# zx80_SD_12_smd_build006_9_STM32.net
KiCad netlist of a schematic drawn in EAGLE
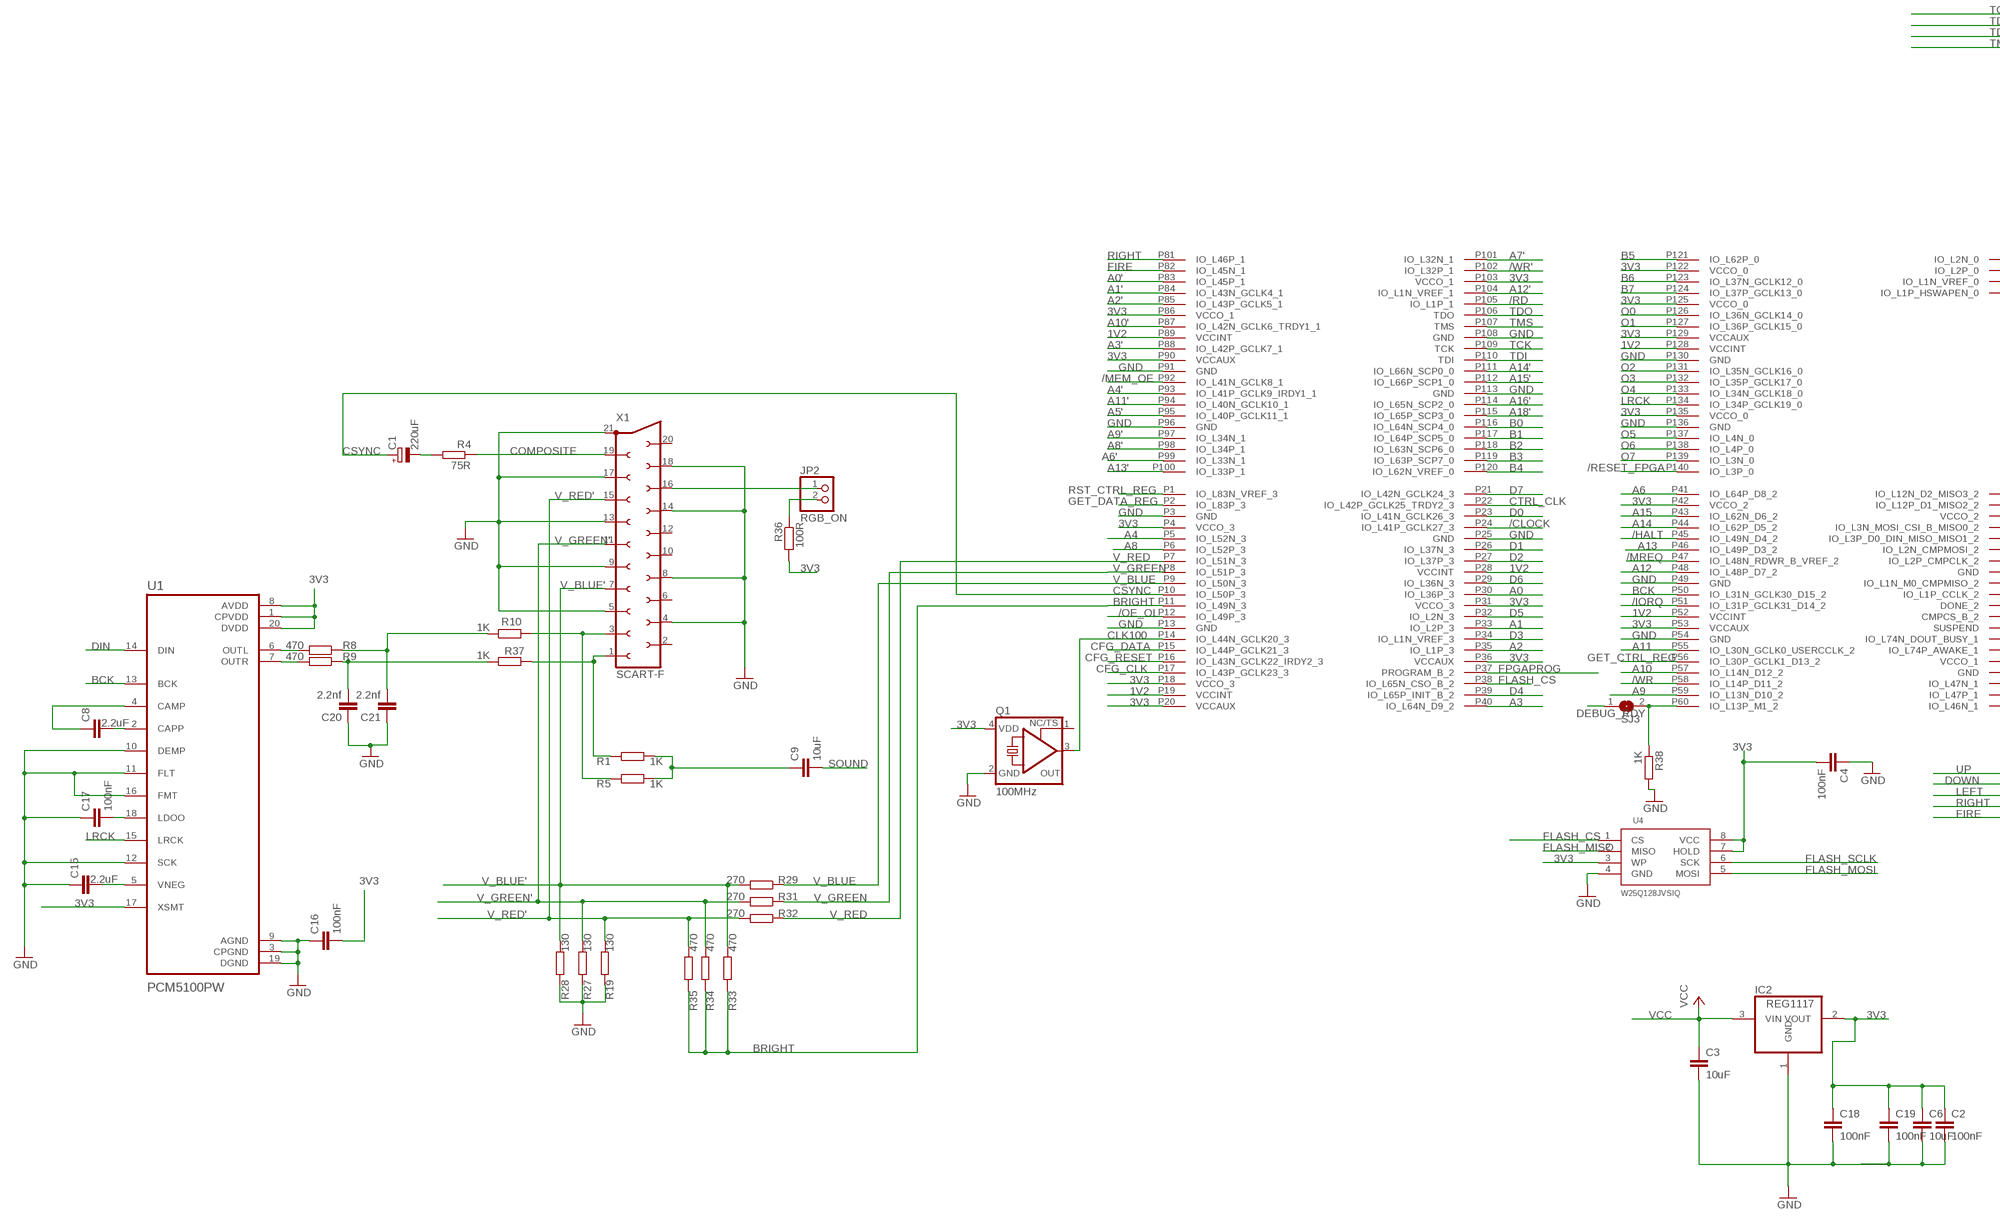
[diagram p0: schematic, sheet 1, part 1 of 2]
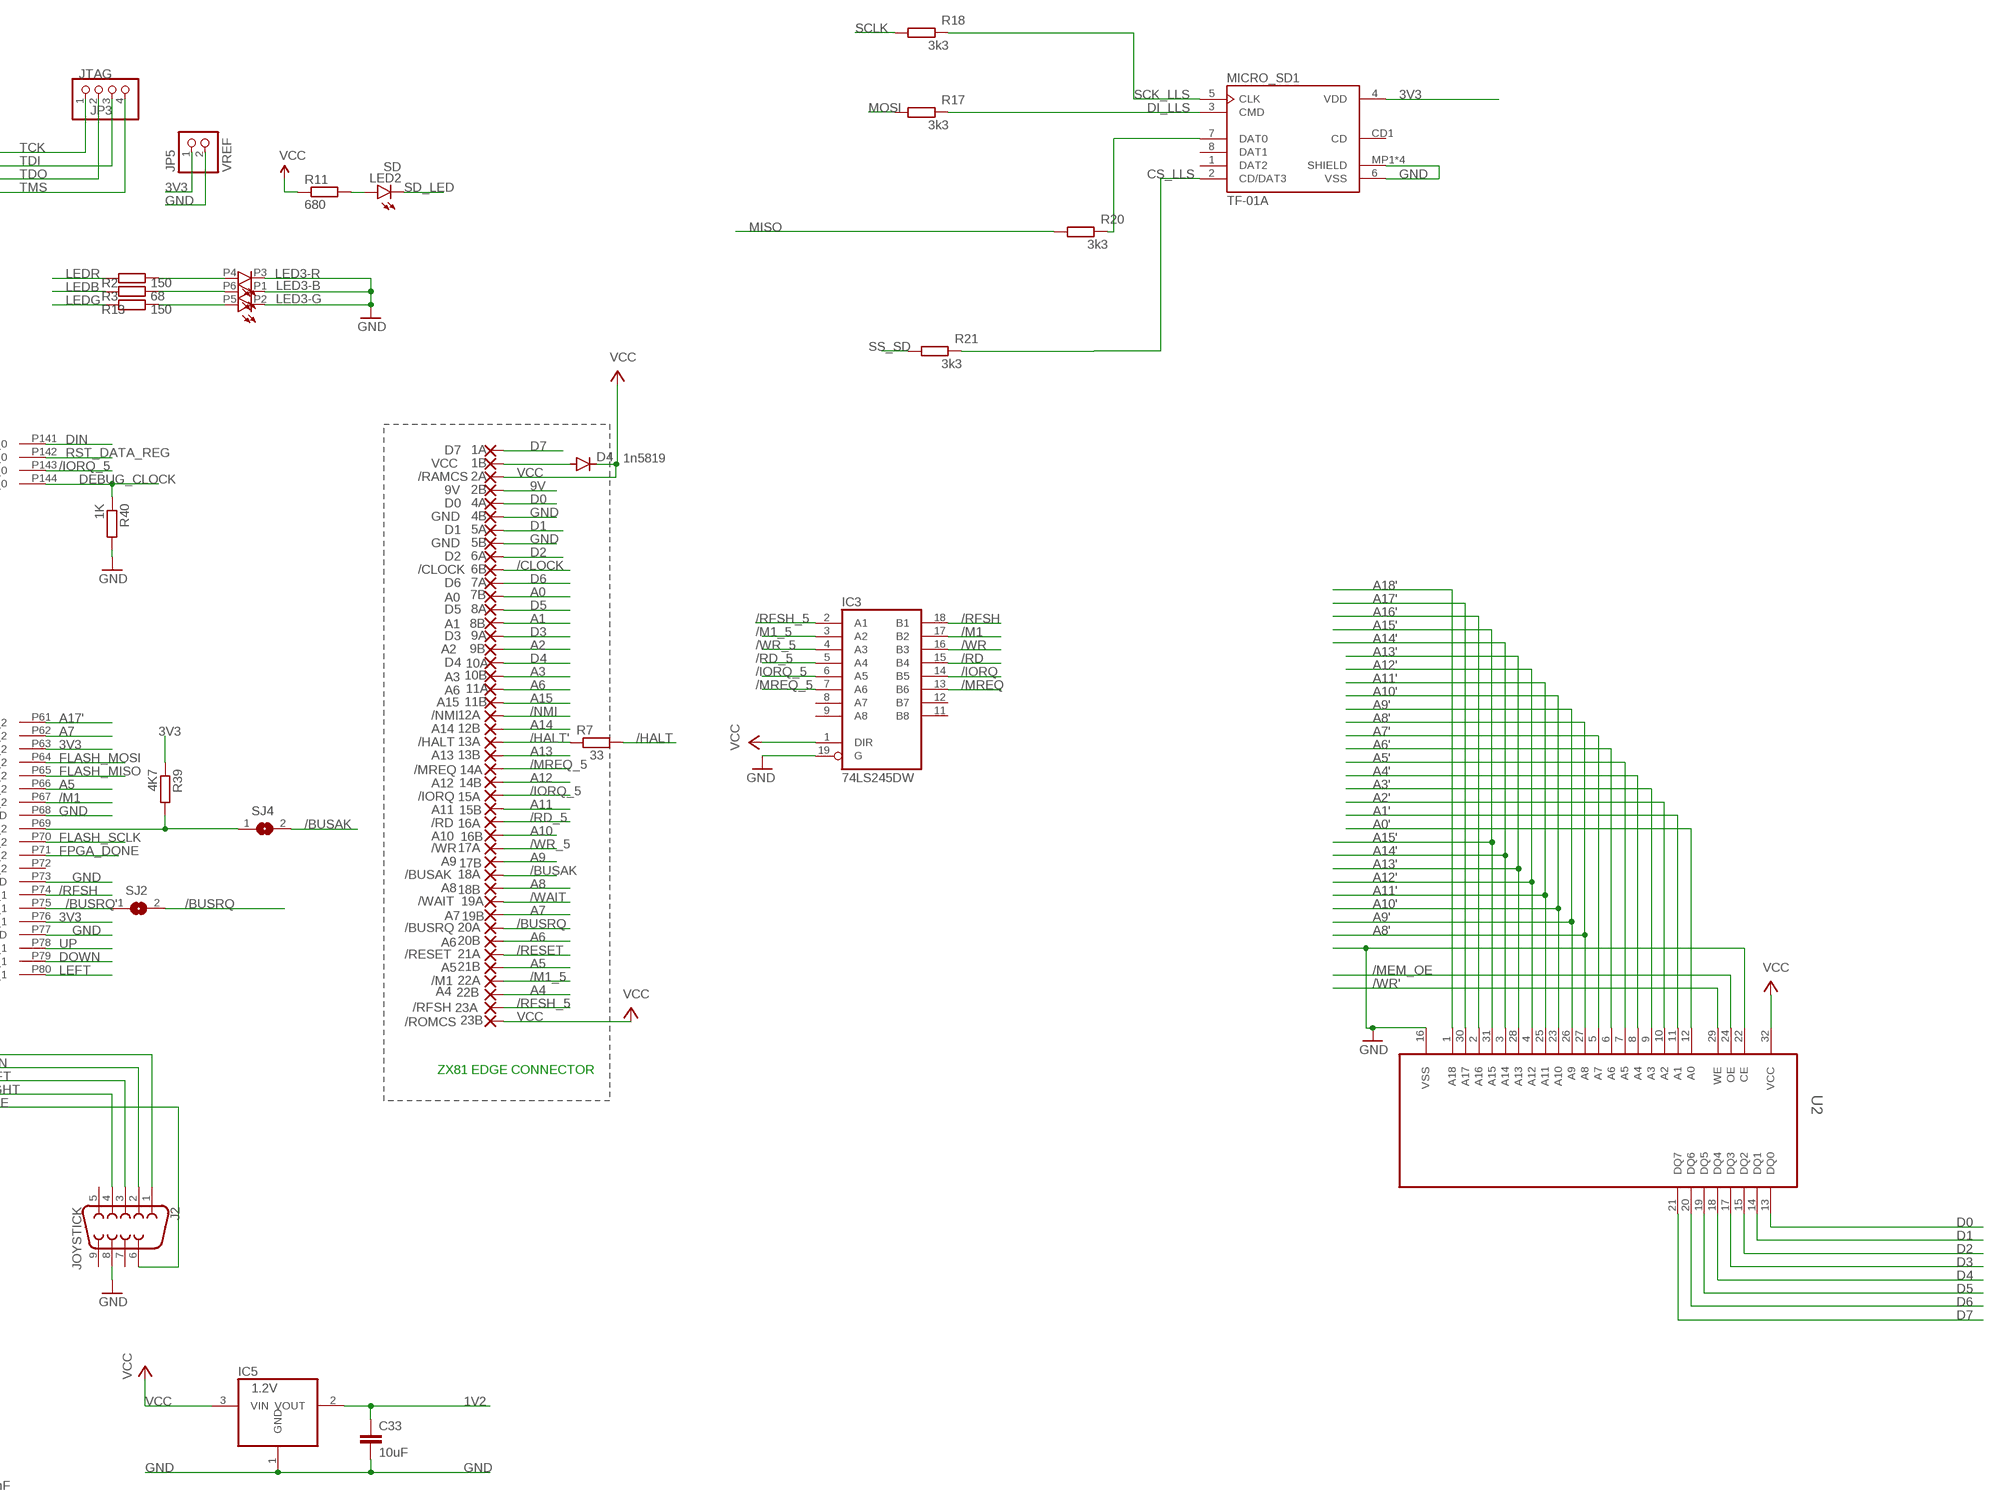
[diagram p1: schematic, sheet 1, part 2 of 2]
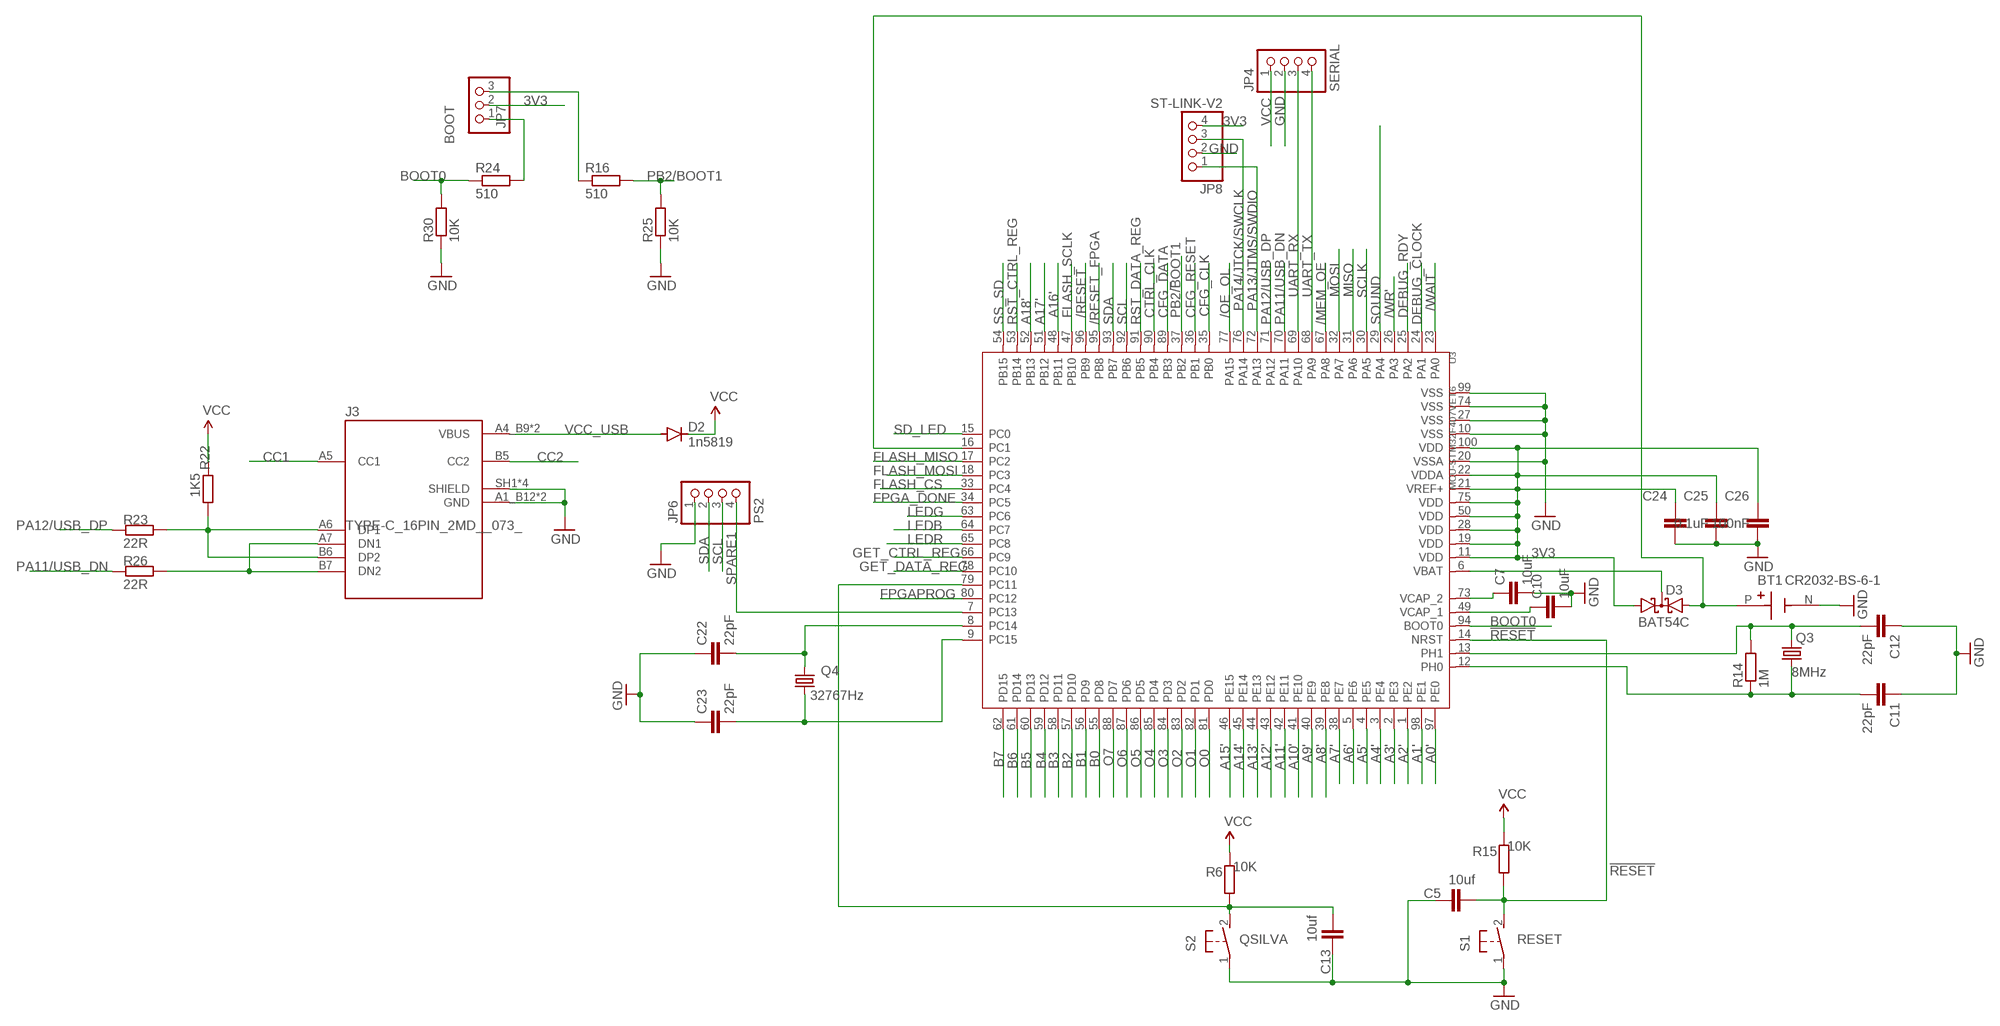
[diagram p2: schematic, sheet 2]

(export (version "E")
  (design (tool "Eeschema 10.0.6"))
  (components
    (comp (ref "BT1")
      (value "CR2032-BS-6-1")
      (footprint "eagle-import:BAT_CR2032-BS-6-1")
      (fields (field (name "MF") "Shenzhen Q&J Electronics Co. Ltd"))
      (libsource (lib "eagle-import") (part "CR2032-BS-6-1"))
    )
    (comp (ref "C5")
      (value "10uf")
      (footprint "eagle-import:C0402K")
      (libsource (lib "eagle-import") (part "C-EUC0402K"))
    )
    (comp (ref "C7")
      (value "10uF")
      (footprint "eagle-import:C0402K")
      (libsource (lib "eagle-import") (part "C-EUC0402K"))
    )
    (comp (ref "C10")
      (value "10uF")
      (footprint "eagle-import:C0402K")
      (libsource (lib "eagle-import") (part "C-EUC0402K"))
    )
    (comp (ref "C11")
      (value "22pF")
      (footprint "eagle-import:C0603")
      (libsource (lib "eagle-import") (part "C-EUC0603"))
    )
    (comp (ref "C12")
      (value "22pF")
      (footprint "eagle-import:C0603")
      (libsource (lib "eagle-import") (part "C-EUC0603"))
    )
    (comp (ref "C13")
      (value "10uf")
      (footprint "eagle-import:C0402K")
      (libsource (lib "eagle-import") (part "C-EUC0402K"))
    )
    (comp (ref "C22")
      (value "22pF")
      (footprint "eagle-import:C0603")
      (libsource (lib "eagle-import") (part "C-EUC0603"))
    )
    (comp (ref "C23")
      (value "22pF")
      (footprint "eagle-import:C0603")
      (libsource (lib "eagle-import") (part "C-EUC0603"))
    )
    (comp (ref "C24")
      (value "0.1uF")
      (footprint "eagle-import:C0402K")
      (libsource (lib "eagle-import") (part "C-EUC0402K"))
    )
    (comp (ref "C25")
      (value "0.1uF")
      (footprint "eagle-import:C0402K")
      (libsource (lib "eagle-import") (part "C-EUC0402K"))
    )
    (comp (ref "C26")
      (value "100nF")
      (footprint "eagle-import:C0402K")
      (libsource (lib "eagle-import") (part "C-EUC0402K"))
    )
    (comp (ref "D2")
      (value "1n5819")
      (footprint "eagle-import:SOD323-W")
      (libsource (lib "eagle-import") (part "DIODE-SOD323-W"))
    )
    (comp (ref "D3")
      (value "BAT54C")
      (footprint "eagle-import:SOT23")
      (libsource (lib "eagle-import") (part "BAT54C"))
    )
    (comp (ref "J3")
      (value "TYPE-C_16PIN_2MD__073_")
      (footprint "eagle-import:SHOUHAN_TYPE-C_16PIN_2MD__073_")
      (fields (field (name "MF") "Shouhan") (field (name "MP") "TYPE-C 16PIN 2MD (073)"))
      (libsource (lib "eagle-import") (part "TYPE-C_16PIN_2MD__073_"))
    )
    (comp (ref "JP4")
      (value "SERIAL")
      (footprint "eagle-import:1X04")
      (libsource (lib "eagle-import") (part "PINHD-1X4"))
    )
    (comp (ref "JP6")
      (value "PS2")
      (footprint "eagle-import:1X04")
      (libsource (lib "eagle-import") (part "PINHD-1X4"))
    )
    (comp (ref "JP7")
      (value "BOOT")
      (footprint "eagle-import:1X03")
      (libsource (lib "eagle-import") (part "PINHD-1X3"))
    )
    (comp (ref "JP8")
      (value "ST-LINK-V2")
      (footprint "eagle-import:1X04")
      (libsource (lib "eagle-import") (part "PINHD-1X4"))
    )
    (comp (ref "Q3")
      (value "8MHz")
      (footprint "eagle-import:3.2X2.5_KX-7")
      (libsource (lib "eagle-import") (part "KX-7"))
    )
    (comp (ref "Q4")
      (value "32767Hz")
      (footprint "eagle-import:3.2X1.5")
      (libsource (lib "eagle-import") (part "KX-327-NHT"))
    )
    (comp (ref "R6")
      (value "10K")
      (footprint "eagle-import:R0402")
      (libsource (lib "eagle-import") (part "R-EU_R0402"))
    )
    (comp (ref "R14")
      (value "1M")
      (footprint "eagle-import:R0402")
      (libsource (lib "eagle-import") (part "R-EU_R0402"))
    )
    (comp (ref "R15")
      (value "10K")
      (footprint "eagle-import:R0402")
      (libsource (lib "eagle-import") (part "R-EU_R0402"))
    )
    (comp (ref "R16")
      (value "510")
      (footprint "eagle-import:R0402")
      (libsource (lib "eagle-import") (part "R-EU_R0402"))
    )
    (comp (ref "R22")
      (value "1K5")
      (footprint "eagle-import:R0402")
      (libsource (lib "eagle-import") (part "R-EU_R0402"))
    )
    (comp (ref "R23")
      (value "22R")
      (footprint "eagle-import:R0402")
      (libsource (lib "eagle-import") (part "R-EU_R0402"))
    )
    (comp (ref "R24")
      (value "510")
      (footprint "eagle-import:R0402")
      (libsource (lib "eagle-import") (part "R-EU_R0402"))
    )
    (comp (ref "R25")
      (value "10K")
      (footprint "eagle-import:R0402")
      (libsource (lib "eagle-import") (part "R-EU_R0402"))
    )
    (comp (ref "R26")
      (value "22R")
      (footprint "eagle-import:R0402")
      (libsource (lib "eagle-import") (part "R-EU_R0402"))
    )
    (comp (ref "R30")
      (value "10K")
      (footprint "eagle-import:R0402")
      (libsource (lib "eagle-import") (part "R-EU_R0402"))
    )
    (comp (ref "S1")
      (value "RESET")
      (footprint "eagle-import:B3F-31XX")
      (fields (field (name "MPN") "B3F-3100"))
      (libsource (lib "eagle-import") (part "31-XX"))
    )
    (comp (ref "S2")
      (value "QSILVA")
      (footprint "eagle-import:B3F-31XX")
      (fields (field (name "MPN") "B3F-3100"))
      (libsource (lib "eagle-import") (part "31-XX"))
    )
    (comp (ref "U3")
      (value "MCU-STM32F407VET6")
      (footprint "eagle-import:LQFP100-0.5-13.8X13.8MM")
      (fields (field (name "MF") "STMicroelectronics") (field (name "MP") "STM32F407VET6"))
      (libsource (lib "eagle-import") (part "MCU-STM32F407VET6(LQFP100)"))
    )
    (comp (ref "1A")
      (value "D7")
      (footprint "eagle-import:EDGEPIN")
      (libsource (lib "eagle-import") (part "SMD2EDGEPIN"))
    )
    (comp (ref "1B")
      (value "VCC")
      (footprint "eagle-import:EDGEPIN")
      (libsource (lib "eagle-import") (part "SMD2EDGEPIN"))
    )
    (comp (ref "2A")
      (value "/RAMCS")
      (footprint "eagle-import:EDGEPIN")
      (libsource (lib "eagle-import") (part "SMD2EDGEPIN"))
    )
    (comp (ref "2B")
      (value "9V")
      (footprint "eagle-import:EDGEPIN")
      (libsource (lib "eagle-import") (part "SMD2EDGEPIN"))
    )
    (comp (ref "4A")
      (value "D0")
      (footprint "eagle-import:EDGEPIN")
      (libsource (lib "eagle-import") (part "SMD2EDGEPIN"))
    )
    (comp (ref "4B")
      (value "GND")
      (footprint "eagle-import:EDGEPIN")
      (libsource (lib "eagle-import") (part "SMD2EDGEPIN"))
    )
    (comp (ref "5A")
      (value "D1")
      (footprint "eagle-import:EDGEPIN")
      (libsource (lib "eagle-import") (part "SMD2EDGEPIN"))
    )
    (comp (ref "5B")
      (value "GND")
      (footprint "eagle-import:EDGEPIN")
      (libsource (lib "eagle-import") (part "SMD2EDGEPIN"))
    )
    (comp (ref "6A")
      (value "D2")
      (footprint "eagle-import:EDGEPIN")
      (libsource (lib "eagle-import") (part "SMD2EDGEPIN"))
    )
    (comp (ref "6B")
      (value "/CLOCK")
      (footprint "eagle-import:EDGEPIN")
      (libsource (lib "eagle-import") (part "SMD2EDGEPIN"))
    )
    (comp (ref "7A")
      (value "D6")
      (footprint "eagle-import:EDGEPIN")
      (libsource (lib "eagle-import") (part "SMD2EDGEPIN"))
    )
    (comp (ref "7B")
      (value "A0")
      (footprint "eagle-import:EDGEPIN")
      (libsource (lib "eagle-import") (part "SMD2EDGEPIN"))
    )
    (comp (ref "8A")
      (value "D5")
      (footprint "eagle-import:EDGEPIN")
      (libsource (lib "eagle-import") (part "SMD2EDGEPIN"))
    )
    (comp (ref "8B")
      (value "A1")
      (footprint "eagle-import:EDGEPIN")
      (libsource (lib "eagle-import") (part "SMD2EDGEPIN"))
    )
    (comp (ref "9A")
      (value "D3")
      (footprint "eagle-import:EDGEPIN")
      (libsource (lib "eagle-import") (part "SMD2EDGEPIN"))
    )
    (comp (ref "9B")
      (value "A2")
      (footprint "eagle-import:EDGEPIN")
      (libsource (lib "eagle-import") (part "SMD2EDGEPIN"))
    )
    (comp (ref "10A")
      (value "D4")
      (footprint "eagle-import:EDGEPIN")
      (libsource (lib "eagle-import") (part "SMD2EDGEPIN"))
    )
    (comp (ref "10B")
      (value "A3")
      (footprint "eagle-import:EDGEPIN")
      (libsource (lib "eagle-import") (part "SMD2EDGEPIN"))
    )
    (comp (ref "11A")
      (value "A6")
      (footprint "eagle-import:EDGEPIN")
      (libsource (lib "eagle-import") (part "SMD2EDGEPIN"))
    )
    (comp (ref "11B")
      (value "A15")
      (footprint "eagle-import:EDGEPIN")
      (libsource (lib "eagle-import") (part "SMD2EDGEPIN"))
    )
    (comp (ref "12A")
      (value "/NMI")
      (footprint "eagle-import:EDGEPIN")
      (libsource (lib "eagle-import") (part "SMD2EDGEPIN"))
    )
    (comp (ref "12B")
      (value "A14")
      (footprint "eagle-import:EDGEPIN")
      (libsource (lib "eagle-import") (part "SMD2EDGEPIN"))
    )
    (comp (ref "13A")
      (value "/HALT")
      (footprint "eagle-import:EDGEPIN")
      (libsource (lib "eagle-import") (part "SMD2EDGEPIN"))
    )
    (comp (ref "13B")
      (value "A13")
      (footprint "eagle-import:EDGEPIN")
      (libsource (lib "eagle-import") (part "SMD2EDGEPIN"))
    )
    (comp (ref "14A")
      (value "/MREQ")
      (footprint "eagle-import:EDGEPIN")
      (libsource (lib "eagle-import") (part "SMD2EDGEPIN"))
    )
    (comp (ref "14B")
      (value "A12")
      (footprint "eagle-import:EDGEPIN")
      (libsource (lib "eagle-import") (part "SMD2EDGEPIN"))
    )
    (comp (ref "15A")
      (value "/IORQ")
      (footprint "eagle-import:EDGEPIN")
      (libsource (lib "eagle-import") (part "SMD2EDGEPIN"))
    )
    (comp (ref "15B")
      (value "A11")
      (footprint "eagle-import:EDGEPIN")
      (libsource (lib "eagle-import") (part "SMD2EDGEPIN"))
    )
    (comp (ref "16A")
      (value "/RD")
      (footprint "eagle-import:EDGEPIN")
      (libsource (lib "eagle-import") (part "SMD2EDGEPIN"))
    )
    (comp (ref "16B")
      (value "A10")
      (footprint "eagle-import:EDGEPIN")
      (libsource (lib "eagle-import") (part "SMD2EDGEPIN"))
    )
    (comp (ref "17A")
      (value "/WR")
      (footprint "eagle-import:EDGEPIN")
      (libsource (lib "eagle-import") (part "SMD2EDGEPIN"))
    )
    (comp (ref "17B")
      (value "A9")
      (footprint "eagle-import:EDGEPIN")
      (libsource (lib "eagle-import") (part "SMD2EDGEPIN"))
    )
    (comp (ref "18A")
      (value "/BUSAK")
      (footprint "eagle-import:EDGEPIN")
      (libsource (lib "eagle-import") (part "SMD2EDGEPIN"))
    )
    (comp (ref "18B")
      (value "A8")
      (footprint "eagle-import:EDGEPIN")
      (libsource (lib "eagle-import") (part "SMD2EDGEPIN"))
    )
    (comp (ref "19A")
      (value "/WAIT")
      (footprint "eagle-import:EDGEPIN")
      (libsource (lib "eagle-import") (part "SMD2EDGEPIN"))
    )
    (comp (ref "19B")
      (value "A7")
      (footprint "eagle-import:EDGEPIN")
      (libsource (lib "eagle-import") (part "SMD2EDGEPIN"))
    )
    (comp (ref "20A")
      (value "/BUSRQ")
      (footprint "eagle-import:EDGEPIN")
      (libsource (lib "eagle-import") (part "SMD2EDGEPIN"))
    )
    (comp (ref "20B")
      (value "A6")
      (footprint "eagle-import:EDGEPIN")
      (libsource (lib "eagle-import") (part "SMD2EDGEPIN"))
    )
    (comp (ref "21A")
      (value "/RESET")
      (footprint "eagle-import:EDGEPIN")
      (libsource (lib "eagle-import") (part "SMD2EDGEPIN"))
    )
    (comp (ref "21B")
      (value "A5")
      (footprint "eagle-import:EDGEPIN")
      (libsource (lib "eagle-import") (part "SMD2EDGEPIN"))
    )
    (comp (ref "22A")
      (value "/M1")
      (footprint "eagle-import:EDGEPIN")
      (libsource (lib "eagle-import") (part "SMD2EDGEPIN"))
    )
    (comp (ref "22B")
      (value "A4")
      (footprint "eagle-import:EDGEPIN")
      (libsource (lib "eagle-import") (part "SMD2EDGEPIN"))
    )
    (comp (ref "23A")
      (value "/RFSH")
      (footprint "eagle-import:EDGEPIN")
      (libsource (lib "eagle-import") (part "SMD2EDGEPIN"))
    )
    (comp (ref "23B")
      (value "/ROMCS")
      (footprint "eagle-import:EDGEPIN")
      (libsource (lib "eagle-import") (part "SMD2EDGEPIN"))
    )
    (comp (ref "C1")
      (value "220uF")
      (footprint "eagle-import:UD-6,3X7,7_NICHICON")
      (libsource (lib "eagle-import") (part "CPOL-EUUD-6,3X7,7"))
    )
    (comp (ref "C2")
      (value "100nF")
      (footprint "eagle-import:C0402K")
      (libsource (lib "eagle-import") (part "C-EUC0402K"))
    )
    (comp (ref "C3")
      (value "10uF")
      (footprint "eagle-import:C0402K")
      (libsource (lib "eagle-import") (part "C-EUC0402K"))
    )
    (comp (ref "C4")
      (value "100nF")
      (footprint "eagle-import:C0402K")
      (libsource (lib "eagle-import") (part "C-EUC0402K"))
    )
    (comp (ref "C6")
      (value "10uF")
      (footprint "eagle-import:C0402K")
      (libsource (lib "eagle-import") (part "C-EUC0402K"))
    )
    (comp (ref "C8")
      (value "2.2uF")
      (footprint "eagle-import:C0402K")
      (libsource (lib "eagle-import") (part "C-EUC0402K"))
    )
    (comp (ref "C9")
      (value "10uF")
      (footprint "eagle-import:C0402K")
      (libsource (lib "eagle-import") (part "C-EUC0402K"))
    )
    (comp (ref "C15")
      (value "2.2uF")
      (footprint "eagle-import:C0402K")
      (libsource (lib "eagle-import") (part "C-EUC0402K"))
    )
    (comp (ref "C16")
      (value "100nF")
      (footprint "eagle-import:C0402K")
      (libsource (lib "eagle-import") (part "C-EUC0402K"))
    )
    (comp (ref "C17")
      (value "100nF")
      (footprint "eagle-import:C0402K")
      (libsource (lib "eagle-import") (part "C-EUC0402K"))
    )
    (comp (ref "C18")
      (value "100nF")
      (footprint "eagle-import:C0402K")
      (libsource (lib "eagle-import") (part "C-EUC0402K"))
    )
    (comp (ref "C19")
      (value "100nF")
      (footprint "eagle-import:C0402K")
      (libsource (lib "eagle-import") (part "C-EUC0402K"))
    )
    (comp (ref "C20")
      (value "2.2nf")
      (footprint "eagle-import:C0603K")
      (libsource (lib "eagle-import") (part "C-EUC0603K"))
    )
    (comp (ref "C21")
      (value "2.2nf")
      (footprint "eagle-import:C0603K")
      (libsource (lib "eagle-import") (part "C-EUC0603K"))
    )
    (comp (ref "C33")
      (value "10uF")
      (footprint "eagle-import:C0402K")
      (libsource (lib "eagle-import") (part "C-EUC0402K"))
    )
    (comp (ref "D4")
      (value "1n5819")
      (footprint "eagle-import:SOD323-W")
      (libsource (lib "eagle-import") (part "DIODE-SOD323-W"))
    )
    (comp (ref "IC2")
      (value "REG1117")
      (footprint "eagle-import:SOT223")
      (libsource (lib "eagle-import") (part "REG1117"))
    )
    (comp (ref "IC3")
      (value "74LS245DW")
      (footprint "eagle-import:SO20W")
      (libsource (lib "eagle-import") (part "74245DWLS"))
    )
    (comp (ref "IC5")
      (value "1.2V")
      (footprint "eagle-import:SOT223")
      (fields (field (name "MPN") "REG1117"))
      (libsource (lib "eagle-import") (part "REG1117"))
    )
    (comp (ref "J2")
      (value "JOYSTICK")
      (footprint "eagle-import:DB9_MALE")
      (libsource (lib "eagle-import") (part "DB9MALE"))
    )
    (comp (ref "JP2")
      (value "RGB_ON")
      (footprint "eagle-import:1X02")
      (libsource (lib "eagle-import") (part "PINHD-1X2"))
    )
    (comp (ref "JP3")
      (value "JTAG")
      (footprint "eagle-import:1X04")
      (libsource (lib "eagle-import") (part "PINHD-1X4"))
    )
    (comp (ref "JP5")
      (value "VREF")
      (footprint "eagle-import:1X02")
      (libsource (lib "eagle-import") (part "PINHD-1X2"))
    )
    (comp (ref "LED2")
      (value "SD")
      (footprint "eagle-import:CHIPLED_0805")
      (libsource (lib "eagle-import") (part "LEDCHIPLED_0805"))
    )
    (comp (ref "LED3")
      (value "STATUS")
      (footprint "eagle-import:3535-PLCC6")
      (libsource (lib "eagle-import") (part "3535RGB3535RGB"))
    )
    (comp (ref "MICRO_SD1")
      (value "TF-01A")
      (footprint "eagle-import:TF-01A")
      (fields (field (name "MF") "HRO Electronics Co., Ltd."))
      (libsource (lib "eagle-import") (part "TF-01A"))
    )
    (comp (ref "Q1")
      (value "100MHz")
      (footprint "eagle-import:3.2X2.5_KXO-V96")
      (libsource (lib "eagle-import") (part "KXO-PXO/XO-V96"))
    )
    (comp (ref "R1")
      (value "1K")
      (footprint "eagle-import:R0402")
      (libsource (lib "eagle-import") (part "R-EU_R0402"))
    )
    (comp (ref "R2")
      (value "150")
      (footprint "eagle-import:R0402")
      (libsource (lib "eagle-import") (part "R-EU_R0402"))
    )
    (comp (ref "R3")
      (value "68")
      (footprint "eagle-import:R0402")
      (libsource (lib "eagle-import") (part "R-EU_R0402"))
    )
    (comp (ref "R4")
      (value "75R")
      (footprint "eagle-import:R0402")
      (libsource (lib "eagle-import") (part "R-EU_R0402"))
    )
    (comp (ref "R5")
      (value "1K")
      (footprint "eagle-import:R0402")
      (libsource (lib "eagle-import") (part "R-EU_R0402"))
    )
    (comp (ref "R7")
      (value "33")
      (footprint "eagle-import:R0402")
      (libsource (lib "eagle-import") (part "R-EU_R0402"))
    )
    (comp (ref "R8")
      (value "470")
      (footprint "eagle-import:R0402")
      (libsource (lib "eagle-import") (part "R-EU_R0402"))
    )
    (comp (ref "R9")
      (value "470")
      (footprint "eagle-import:R0402")
      (libsource (lib "eagle-import") (part "R-EU_R0402"))
    )
    (comp (ref "R10")
      (value "1K")
      (footprint "eagle-import:R0402")
      (libsource (lib "eagle-import") (part "R-EU_R0402"))
    )
    (comp (ref "R11")
      (value "680")
      (footprint "eagle-import:R0402")
      (libsource (lib "eagle-import") (part "R-EU_R0402"))
    )
    (comp (ref "R13")
      (value "150")
      (footprint "eagle-import:R0402")
      (libsource (lib "eagle-import") (part "R-EU_R0402"))
    )
    (comp (ref "R17")
      (value "3k3")
      (footprint "eagle-import:R0402")
      (libsource (lib "eagle-import") (part "R-EU_R0402"))
    )
    (comp (ref "R18")
      (value "3k3")
      (footprint "eagle-import:R0402")
      (libsource (lib "eagle-import") (part "R-EU_R0402"))
    )
    (comp (ref "R19")
      (value "130")
      (footprint "eagle-import:R0402")
      (libsource (lib "eagle-import") (part "R-EU_R0402"))
    )
    (comp (ref "R20")
      (value "3k3")
      (footprint "eagle-import:R0402")
      (libsource (lib "eagle-import") (part "R-EU_R0402"))
    )
    (comp (ref "R21")
      (value "3k3")
      (footprint "eagle-import:R0402")
      (libsource (lib "eagle-import") (part "R-EU_R0402"))
    )
    (comp (ref "R27")
      (value "130")
      (footprint "eagle-import:R0402")
      (libsource (lib "eagle-import") (part "R-EU_R0402"))
    )
    (comp (ref "R28")
      (value "130")
      (footprint "eagle-import:R0402")
      (libsource (lib "eagle-import") (part "R-EU_R0402"))
    )
    (comp (ref "R29")
      (value "270")
      (footprint "eagle-import:R0402")
      (libsource (lib "eagle-import") (part "R-EU_R0402"))
    )
    (comp (ref "R31")
      (value "270")
      (footprint "eagle-import:R0402")
      (libsource (lib "eagle-import") (part "R-EU_R0402"))
    )
    (comp (ref "R32")
      (value "270")
      (footprint "eagle-import:R0402")
      (libsource (lib "eagle-import") (part "R-EU_R0402"))
    )
    (comp (ref "R33")
      (value "470")
      (footprint "eagle-import:R0402")
      (libsource (lib "eagle-import") (part "R-EU_R0402"))
    )
    (comp (ref "R34")
      (value "470")
      (footprint "eagle-import:R0402")
      (libsource (lib "eagle-import") (part "R-EU_R0402"))
    )
    (comp (ref "R35")
      (value "470")
      (footprint "eagle-import:R0402")
      (libsource (lib "eagle-import") (part "R-EU_R0402"))
    )
    (comp (ref "R36")
      (value "100R")
      (footprint "eagle-import:R0402")
      (libsource (lib "eagle-import") (part "R-EU_R0402"))
    )
    (comp (ref "R37")
      (value "1K")
      (footprint "eagle-import:R0402")
      (libsource (lib "eagle-import") (part "R-EU_R0402"))
    )
    (comp (ref "R38")
      (value "1K")
      (footprint "eagle-import:R0402")
      (libsource (lib "eagle-import") (part "R-EU_R0402"))
    )
    (comp (ref "R39")
      (value "4K7")
      (footprint "eagle-import:R0402")
      (libsource (lib "eagle-import") (part "R-EU_R0402"))
    )
    (comp (ref "R40")
      (value "1K")
      (footprint "eagle-import:R0402")
      (libsource (lib "eagle-import") (part "R-EU_R0402"))
    )
    (comp (ref "SJ2") (value "SJ") (footprint "eagle-import:SJ") (libsource (lib "eagle-import") (part "SJ")))
    (comp (ref "SJ3") (value "SJ") (footprint "eagle-import:SJ") (libsource (lib "eagle-import") (part "SJ")))
    (comp (ref "SJ4") (value "SJ") (footprint "eagle-import:SJ") (libsource (lib "eagle-import") (part "SJ")))
    (comp (ref "U1")
      (value "PCM5100PW")
      (footprint "eagle-import:SOP65P640X120-20N")
      (fields (field (name "MF") "Texas Instruments"))
      (libsource (lib "eagle-import") (part "PCM5100PW"))
    )
    (comp (ref "U2")
      (value "AS6C4008")
      (footprint "eagle-import:SOP32-5")
      (libsource (lib "eagle-import") (part "AS6C4008-55SINSOP5"))
    )
    (comp (ref "U4")
      (value "W25Q128JVSIQ")
      (footprint "eagle-import:SO08-EIAJ")
      (libsource (lib "eagle-import") (part "SPI_FLASH-X25XXSMD1"))
    )
    (comp (ref "U6")
      (value "XC6SLX9-2TQG144C")
      (footprint "eagle-import:TQ144")
      (fields (field (name "MF") "Xilinx Inc."))
      (libsource (lib "eagle-import") (part "XC6SLX9-2TQG144C"))
    )
    (comp (ref "X1")
      (value "SCART-F")
      (footprint "eagle-import:SCART-F")
      (libsource (lib "eagle-import") (part "SCART-F"))
    )
  )
  (nets
    (net (code "1") (name "1V2") (class "Default")
      (node (ref "C33") (pin "1") (pinfunction "1_1") (pintype "passive"))
      (node (ref "IC5") (pin "2") (pinfunction "VOUT_2") (pintype "output"))
      (node (ref "U6") (pin "P128") (pinfunction "VCCINT_P128") (pintype "bidirectional"))
      (node (ref "U6") (pin "P19") (pinfunction "VCCINT_P19") (pintype "bidirectional"))
      (node (ref "U6") (pin "P28") (pinfunction "VCCINT_P28") (pintype "bidirectional"))
      (node (ref "U6") (pin "P52") (pinfunction "VCCINT_P52") (pintype "bidirectional"))
      (node (ref "U6") (pin "P89") (pinfunction "VCCINT_P89") (pintype "bidirectional"))
    )
    (net (code "2") (name "3V3") (class "Default")
      (node (ref "C16") (pin "2") (pinfunction "2_2") (pintype "passive"))
      (node (ref "C18") (pin "1") (pinfunction "1_1") (pintype "passive"))
      (node (ref "C19") (pin "1") (pinfunction "1_1") (pintype "passive"))
      (node (ref "C2") (pin "1") (pinfunction "1_1") (pintype "passive"))
      (node (ref "C24") (pin "1") (pinfunction "1_1") (pintype "passive"))
      (node (ref "C25") (pin "1") (pinfunction "1_1") (pintype "passive"))
      (node (ref "C26") (pin "1") (pinfunction "1_1") (pintype "passive"))
      (node (ref "C4") (pin "2") (pinfunction "2_2") (pintype "passive"))
      (node (ref "C6") (pin "1") (pinfunction "1_1") (pintype "passive"))
      (node (ref "D3") (pin "1") (pinfunction "A1_1") (pintype "passive"))
      (node (ref "IC2") (pin "2") (pinfunction "VOUT_2") (pintype "output"))
      (node (ref "JP5") (pin "1") (pinfunction "1_1") (pintype "passive"))
      (node (ref "JP7") (pin "2") (pinfunction "2_2") (pintype "passive"))
      (node (ref "JP8") (pin "4") (pinfunction "4_4") (pintype "passive"))
      (node (ref "MICRO_SD1") (pin "4") (pinfunction "VDD_4") (pintype "power_in"))
      (node (ref "Q1") (pin "4") (pinfunction "VDD_4") (pintype "power_in"))
      (node (ref "R36") (pin "2") (pinfunction "2_2") (pintype "passive"))
      (node (ref "R39") (pin "1") (pinfunction "1_1") (pintype "passive"))
      (node (ref "U1") (pin "1") (pinfunction "CPVDD_1") (pintype "power_in"))
      (node (ref "U1") (pin "17") (pinfunction "XSMT_17") (pintype "bidirectional"))
      (node (ref "U1") (pin "20") (pinfunction "DVDD_20") (pintype "power_in"))
      (node (ref "U1") (pin "8") (pinfunction "AVDD_8") (pintype "power_in"))
      (node (ref "U3") (pin "100") (pinfunction "VDD_100") (pintype "bidirectional"))
      (node (ref "U3") (pin "11") (pinfunction "VDD_11") (pintype "bidirectional"))
      (node (ref "U3") (pin "19") (pinfunction "VDD_19") (pintype "bidirectional"))
      (node (ref "U3") (pin "21") (pinfunction "VREF+_21") (pintype "bidirectional"))
      (node (ref "U3") (pin "22") (pinfunction "VDDA_22") (pintype "bidirectional"))
      (node (ref "U3") (pin "28") (pinfunction "VDD_28") (pintype "bidirectional"))
      (node (ref "U3") (pin "50") (pinfunction "VDD_50") (pintype "bidirectional"))
      (node (ref "U3") (pin "75") (pinfunction "VDD_75") (pintype "bidirectional"))
      (node (ref "U4") (pin "3") (pinfunction "WP_3") (pintype "bidirectional"))
      (node (ref "U4") (pin "7") (pinfunction "HOLD_7") (pintype "bidirectional"))
      (node (ref "U4") (pin "8") (pinfunction "VCC_8") (pintype "power_in"))
      (node (ref "U6") (pin "P103") (pinfunction "VCCO_1_P103") (pintype "bidirectional"))
      (node (ref "U6") (pin "P122") (pinfunction "VCCO_0_P122") (pintype "bidirectional"))
      (node (ref "U6") (pin "P125") (pinfunction "VCCO_0_P125") (pintype "bidirectional"))
      (node (ref "U6") (pin "P129") (pinfunction "VCCAUX_P129") (pintype "bidirectional"))
      (node (ref "U6") (pin "P135") (pinfunction "VCCO_0_P135") (pintype "bidirectional"))
      (node (ref "U6") (pin "P18") (pinfunction "VCCO_3_P18") (pintype "bidirectional"))
      (node (ref "U6") (pin "P20") (pinfunction "VCCAUX_P20") (pintype "bidirectional"))
      (node (ref "U6") (pin "P31") (pinfunction "VCCO_3_P31") (pintype "bidirectional"))
      (node (ref "U6") (pin "P36") (pinfunction "VCCAUX_P36") (pintype "bidirectional"))
      (node (ref "U6") (pin "P4") (pinfunction "VCCO_3_P4") (pintype "bidirectional"))
      (node (ref "U6") (pin "P42") (pinfunction "VCCO_2_P42") (pintype "bidirectional"))
      (node (ref "U6") (pin "P53") (pinfunction "VCCAUX_P53") (pintype "bidirectional"))
      (node (ref "U6") (pin "P63") (pinfunction "VCCO_2_P63") (pintype "bidirectional"))
      (node (ref "U6") (pin "P76") (pinfunction "VCCO_1_P76") (pintype "bidirectional"))
      (node (ref "U6") (pin "P86") (pinfunction "VCCO_1_P86") (pintype "bidirectional"))
      (node (ref "U6") (pin "P90") (pinfunction "VCCAUX_P90") (pintype "bidirectional"))
    )
    (net (code "3") (name "9V") (class "Default")
      (node (ref "2B") (pin "1") (pinfunction "P_1") (pintype "passive"))
    )
    (net (code "4") (name "A0") (class "Default")
      (node (ref "7B") (pin "1") (pinfunction "P_1") (pintype "passive"))
      (node (ref "U6") (pin "P30") (pinfunction "IO_L36P_3_P30") (pintype "bidirectional"))
    )
    (net (code "5") (name "A0'") (class "Default")
      (node (ref "U2") (pin "12") (pinfunction "A0_12") (pintype "input"))
      (node (ref "U3") (pin "97") (pinfunction "PE0_97") (pintype "bidirectional"))
      (node (ref "U6") (pin "P83") (pinfunction "IO_L45P_1_P83") (pintype "bidirectional"))
    )
    (net (code "6") (name "A1") (class "Default")
      (node (ref "8B") (pin "1") (pinfunction "P_1") (pintype "passive"))
      (node (ref "U6") (pin "P33") (pinfunction "IO_L2P_3_P33") (pintype "bidirectional"))
    )
    (net (code "7") (name "A1'") (class "Default")
      (node (ref "U2") (pin "11") (pinfunction "A1_11") (pintype "input"))
      (node (ref "U3") (pin "98") (pinfunction "PE1_98") (pintype "bidirectional"))
      (node (ref "U6") (pin "P84") (pinfunction "IO_L43N_GCLK4_1_P84") (pintype "bidirectional"))
    )
    (net (code "8") (name "A2") (class "Default")
      (node (ref "9B") (pin "1") (pinfunction "P_1") (pintype "passive"))
      (node (ref "U6") (pin "P35") (pinfunction "IO_L1P_3_P35") (pintype "bidirectional"))
    )
    (net (code "9") (name "A2'") (class "Default")
      (node (ref "U2") (pin "10") (pinfunction "A2_10") (pintype "input"))
      (node (ref "U3") (pin "1") (pinfunction "PE2_1") (pintype "bidirectional"))
      (node (ref "U6") (pin "P85") (pinfunction "IO_L43P_GCLK5_1_P85") (pintype "bidirectional"))
    )
    (net (code "10") (name "A3") (class "Default")
      (node (ref "10B") (pin "1") (pinfunction "P_1") (pintype "passive"))
      (node (ref "U6") (pin "P40") (pinfunction "IO_L64N_D9_2_P40") (pintype "bidirectional"))
    )
    (net (code "11") (name "A3'") (class "Default")
      (node (ref "U2") (pin "9") (pinfunction "A3_9") (pintype "input"))
      (node (ref "U3") (pin "2") (pinfunction "PE3_2") (pintype "bidirectional"))
      (node (ref "U6") (pin "P88") (pinfunction "IO_L42P_GCLK7_1_P88") (pintype "bidirectional"))
    )
    (net (code "12") (name "A4") (class "Default")
      (node (ref "22B") (pin "1") (pinfunction "P_1") (pintype "passive"))
      (node (ref "U6") (pin "P5") (pinfunction "IO_L52N_3_P5") (pintype "bidirectional"))
    )
    (net (code "13") (name "A4'") (class "Default")
      (node (ref "U2") (pin "8") (pinfunction "A4_8") (pintype "input"))
      (node (ref "U3") (pin "3") (pinfunction "PE4_3") (pintype "bidirectional"))
      (node (ref "U6") (pin "P93") (pinfunction "IO_L41P_GCLK9_IRDY1_1_P93") (pintype "bidirectional"))
    )
    (net (code "14") (name "A5") (class "Default")
      (node (ref "21B") (pin "1") (pinfunction "P_1") (pintype "passive"))
      (node (ref "U6") (pin "P66") (pinfunction "IO_L2N_CMPMOSI_2_P66") (pintype "bidirectional"))
    )
    (net (code "15") (name "A5'") (class "Default")
      (node (ref "U2") (pin "7") (pinfunction "A5_7") (pintype "input"))
      (node (ref "U3") (pin "4") (pinfunction "PE5_4") (pintype "bidirectional"))
      (node (ref "U6") (pin "P95") (pinfunction "IO_L40P_GCLK11_1_P95") (pintype "bidirectional"))
    )
    (net (code "16") (name "A6") (class "Default")
      (node (ref "11A") (pin "1") (pinfunction "P_1") (pintype "passive"))
      (node (ref "20B") (pin "1") (pinfunction "P_1") (pintype "passive"))
      (node (ref "U6") (pin "P41") (pinfunction "IO_L64P_D8_2_P41") (pintype "bidirectional"))
    )
    (net (code "17") (name "A6'") (class "Default")
      (node (ref "U2") (pin "6") (pinfunction "A6_6") (pintype "input"))
      (node (ref "U3") (pin "5") (pinfunction "PE6_5") (pintype "bidirectional"))
      (node (ref "U6") (pin "P99") (pinfunction "IO_L33N_1_P99") (pintype "bidirectional"))
    )
    (net (code "18") (name "A7") (class "Default")
      (node (ref "19B") (pin "1") (pinfunction "P_1") (pintype "passive"))
      (node (ref "U6") (pin "P62") (pinfunction "IO_L12P_D1_MISO2_2_P62") (pintype "bidirectional"))
    )
    (net (code "19") (name "A7'") (class "Default")
      (node (ref "U2") (pin "5") (pinfunction "A7_5") (pintype "input"))
      (node (ref "U3") (pin "38") (pinfunction "PE7_38") (pintype "bidirectional"))
      (node (ref "U6") (pin "P101") (pinfunction "IO_L32N_1_P101") (pintype "bidirectional"))
    )
    (net (code "20") (name "A8") (class "Default")
      (node (ref "18B") (pin "1") (pinfunction "P_1") (pintype "passive"))
      (node (ref "U6") (pin "P6") (pinfunction "IO_L52P_3_P6") (pintype "bidirectional"))
    )
    (net (code "21") (name "A8'") (class "Default")
      (node (ref "U2") (pin "27") (pinfunction "A8_27") (pintype "input"))
      (node (ref "U3") (pin "39") (pinfunction "PE8_39") (pintype "bidirectional"))
      (node (ref "U6") (pin "P98") (pinfunction "IO_L34P_1_P98") (pintype "bidirectional"))
    )
    (net (code "22") (name "A9") (class "Default")
      (node (ref "17B") (pin "1") (pinfunction "P_1") (pintype "passive"))
      (node (ref "U6") (pin "P59") (pinfunction "IO_L13N_D10_2_P59") (pintype "bidirectional"))
    )
    (net (code "23") (name "A9'") (class "Default")
      (node (ref "U2") (pin "26") (pinfunction "A9_26") (pintype "input"))
      (node (ref "U3") (pin "40") (pinfunction "PE9_40") (pintype "bidirectional"))
      (node (ref "U6") (pin "P97") (pinfunction "IO_L34N_1_P97") (pintype "bidirectional"))
    )
    (net (code "24") (name "A10") (class "Default")
      (node (ref "16B") (pin "1") (pinfunction "P_1") (pintype "passive"))
      (node (ref "U6") (pin "P57") (pinfunction "IO_L14N_D12_2_P57") (pintype "bidirectional"))
    )
    (net (code "25") (name "A10'") (class "Default")
      (node (ref "U2") (pin "23") (pinfunction "A10_23") (pintype "input"))
      (node (ref "U3") (pin "41") (pinfunction "PE10_41") (pintype "bidirectional"))
      (node (ref "U6") (pin "P87") (pinfunction "IO_L42N_GCLK6_TRDY1_1_P87") (pintype "bidirectional"))
    )
    (net (code "26") (name "A11") (class "Default")
      (node (ref "15B") (pin "1") (pinfunction "P_1") (pintype "passive"))
      (node (ref "U6") (pin "P55") (pinfunction "IO_L30N_GCLK0_USERCCLK_2_P55") (pintype "bidirectional"))
    )
    (net (code "27") (name "A11'") (class "Default")
      (node (ref "U2") (pin "25") (pinfunction "A11_25") (pintype "input"))
      (node (ref "U3") (pin "42") (pinfunction "PE11_42") (pintype "bidirectional"))
      (node (ref "U6") (pin "P94") (pinfunction "IO_L40N_GCLK10_1_P94") (pintype "bidirectional"))
    )
    (net (code "28") (name "A12") (class "Default")
      (node (ref "14B") (pin "1") (pinfunction "P_1") (pintype "passive"))
      (node (ref "U6") (pin "P48") (pinfunction "IO_L48P_D7_2_P48") (pintype "bidirectional"))
    )
    (net (code "29") (name "A12'") (class "Default")
      (node (ref "U2") (pin "4") (pinfunction "A12_4") (pintype "input"))
      (node (ref "U3") (pin "43") (pinfunction "PE12_43") (pintype "bidirectional"))
      (node (ref "U6") (pin "P104") (pinfunction "IO_L1N_VREF_1_P104") (pintype "bidirectional"))
    )
    (net (code "30") (name "A13") (class "Default")
      (node (ref "13B") (pin "1") (pinfunction "P_1") (pintype "passive"))
      (node (ref "U6") (pin "P46") (pinfunction "IO_L49P_D3_2_P46") (pintype "bidirectional"))
    )
    (net (code "31") (name "A13'") (class "Default")
      (node (ref "U2") (pin "28") (pinfunction "A13_28") (pintype "input"))
      (node (ref "U3") (pin "44") (pinfunction "PE13_44") (pintype "bidirectional"))
      (node (ref "U6") (pin "P100") (pinfunction "IO_L33P_1_P100") (pintype "bidirectional"))
    )
    (net (code "32") (name "A14") (class "Default")
      (node (ref "12B") (pin "1") (pinfunction "P_1") (pintype "passive"))
      (node (ref "U6") (pin "P44") (pinfunction "IO_L62P_D5_2_P44") (pintype "bidirectional"))
    )
    (net (code "33") (name "A14'") (class "Default")
      (node (ref "U2") (pin "3") (pinfunction "A14_3") (pintype "input"))
      (node (ref "U3") (pin "45") (pinfunction "PE14_45") (pintype "bidirectional"))
      (node (ref "U6") (pin "P111") (pinfunction "IO_L66N_SCP0_0_P111") (pintype "bidirectional"))
    )
    (net (code "34") (name "A15") (class "Default")
      (node (ref "11B") (pin "1") (pinfunction "P_1") (pintype "passive"))
      (node (ref "U6") (pin "P43") (pinfunction "IO_L62N_D6_2_P43") (pintype "bidirectional"))
    )
    (net (code "35") (name "A15'") (class "Default")
      (node (ref "U2") (pin "31") (pinfunction "A15_31") (pintype "input"))
      (node (ref "U3") (pin "46") (pinfunction "PE15_46") (pintype "bidirectional"))
      (node (ref "U6") (pin "P112") (pinfunction "IO_L66P_SCP1_0_P112") (pintype "bidirectional"))
    )
    (net (code "36") (name "A16'") (class "Default")
      (node (ref "U2") (pin "2") (pinfunction "A16_2") (pintype "input"))
      (node (ref "U3") (pin "48") (pinfunction "PB11_48") (pintype "bidirectional"))
      (node (ref "U6") (pin "P114") (pinfunction "IO_L65N_SCP2_0_P114") (pintype "bidirectional"))
    )
    (net (code "37") (name "A17'") (class "Default")
      (node (ref "U2") (pin "30") (pinfunction "A17_30") (pintype "input"))
      (node (ref "U3") (pin "51") (pinfunction "PB12_51") (pintype "bidirectional"))
      (node (ref "U6") (pin "P61") (pinfunction "IO_L12N_D2_MISO3_2_P61") (pintype "bidirectional"))
    )
    (net (code "38") (name "A18'") (class "Default")
      (node (ref "U2") (pin "1") (pinfunction "A18_1") (pintype "input"))
      (node (ref "U3") (pin "52") (pinfunction "PB13_52") (pintype "bidirectional"))
      (node (ref "U6") (pin "P115") (pinfunction "IO_L65P_SCP3_0_P115") (pintype "bidirectional"))
    )
    (net (code "39") (name "B0") (class "Default")
      (node (ref "U3") (pin "55") (pinfunction "PD8_55") (pintype "bidirectional"))
      (node (ref "U6") (pin "P116") (pinfunction "IO_L64N_SCP4_0_P116") (pintype "bidirectional"))
    )
    (net (code "40") (name "B1") (class "Default")
      (node (ref "U3") (pin "56") (pinfunction "PD9_56") (pintype "bidirectional"))
      (node (ref "U6") (pin "P117") (pinfunction "IO_L64P_SCP5_0_P117") (pintype "bidirectional"))
    )
    (net (code "41") (name "B2") (class "Default")
      (node (ref "U3") (pin "57") (pinfunction "PD10_57") (pintype "bidirectional"))
      (node (ref "U6") (pin "P118") (pinfunction "IO_L63N_SCP6_0_P118") (pintype "bidirectional"))
    )
    (net (code "42") (name "B3") (class "Default")
      (node (ref "U3") (pin "58") (pinfunction "PD11_58") (pintype "bidirectional"))
      (node (ref "U6") (pin "P119") (pinfunction "IO_L63P_SCP7_0_P119") (pintype "bidirectional"))
    )
    (net (code "43") (name "B4") (class "Default")
      (node (ref "U3") (pin "59") (pinfunction "PD12_59") (pintype "bidirectional"))
      (node (ref "U6") (pin "P120") (pinfunction "IO_L62N_VREF_0_P120") (pintype "bidirectional"))
    )
    (net (code "44") (name "B5") (class "Default")
      (node (ref "U3") (pin "60") (pinfunction "PD13_60") (pintype "bidirectional"))
      (node (ref "U6") (pin "P121") (pinfunction "IO_L62P_0_P121") (pintype "bidirectional"))
    )
    (net (code "45") (name "B6") (class "Default")
      (node (ref "U3") (pin "61") (pinfunction "PD14_61") (pintype "bidirectional"))
      (node (ref "U6") (pin "P123") (pinfunction "IO_L37N_GCLK12_0_P123") (pintype "bidirectional"))
    )
    (net (code "46") (name "B7") (class "Default")
      (node (ref "U3") (pin "62") (pinfunction "PD15_62") (pintype "bidirectional"))
      (node (ref "U6") (pin "P124") (pinfunction "IO_L37P_GCLK13_0_P124") (pintype "bidirectional"))
    )
    (net (code "47") (name "BCK") (class "Default")
      (node (ref "U1") (pin "13") (pinfunction "BCK_13") (pintype "bidirectional"))
      (node (ref "U6") (pin "P50") (pinfunction "IO_L31N_GCLK30_D15_2_P50") (pintype "bidirectional"))
    )
    (net (code "48") (name "BOOT0") (class "Default")
      (node (ref "R24") (pin "1") (pinfunction "1_1") (pintype "passive"))
      (node (ref "R30") (pin "2") (pinfunction "2_2") (pintype "passive"))
      (node (ref "U3") (pin "94") (pinfunction "BOOT0_94") (pintype "bidirectional"))
    )
    (net (code "49") (name "BRIGHT") (class "Default")
      (node (ref "R33") (pin "1") (pinfunction "1_1") (pintype "passive"))
      (node (ref "R34") (pin "1") (pinfunction "1_1") (pintype "passive"))
      (node (ref "R35") (pin "1") (pinfunction "1_1") (pintype "passive"))
      (node (ref "U6") (pin "P11") (pinfunction "IO_L49N_3_P11") (pintype "bidirectional"))
    )
    (net (code "50") (name "CC1") (class "Default")
      (node (ref "J3") (pin "A5") (pinfunction "CC1_A5") (pintype "bidirectional"))
    )
    (net (code "51") (name "CC2") (class "Default")
      (node (ref "J3") (pin "B5") (pinfunction "CC2_B5") (pintype "bidirectional"))
    )
    (net (code "52") (name "CFG_CLK") (class "Default")
      (node (ref "U3") (pin "35") (pinfunction "PB0_35") (pintype "bidirectional"))
      (node (ref "U6") (pin "P17") (pinfunction "IO_L43P_GCLK23_3_P17") (pintype "bidirectional"))
    )
    (net (code "53") (name "CFG_DATA") (class "Default")
      (node (ref "U3") (pin "89") (pinfunction "PB3_89") (pintype "bidirectional"))
      (node (ref "U6") (pin "P15") (pinfunction "IO_L44P_GCLK21_3_P15") (pintype "bidirectional"))
    )
    (net (code "54") (name "CFG_RESET") (class "Default")
      (node (ref "U3") (pin "36") (pinfunction "PB1_36") (pintype "bidirectional"))
      (node (ref "U6") (pin "P16") (pinfunction "IO_L43N_GCLK22_IRDY2_3_P16") (pintype "bidirectional"))
    )
    (net (code "55") (name "CLK100") (class "Default")
      (node (ref "Q1") (pin "3") (pinfunction "OUT_3") (pintype "output"))
      (node (ref "U6") (pin "P14") (pinfunction "IO_L44N_GCLK20_3_P14") (pintype "bidirectional"))
    )
    (net (code "56") (name "COMPOSITE") (class "Default")
      (node (ref "R4") (pin "1") (pinfunction "1_1") (pintype "passive"))
      (node (ref "X1") (pin "19") (pinfunction "19_19") (pintype "passive"))
    )
    (net (code "57") (name "CSYNC") (class "Default")
      (node (ref "C1") (pin "+") (pinfunction "+_+") (pintype "passive"))
      (node (ref "U6") (pin "P10") (pinfunction "IO_L50P_3_P10") (pintype "bidirectional"))
    )
    (net (code "58") (name "CS_LLS") (class "Default")
      (node (ref "MICRO_SD1") (pin "2") (pinfunction "CD/DAT3_2") (pintype "bidirectional"))
      (node (ref "R21") (pin "2") (pinfunction "2_2") (pintype "passive"))
    )
    (net (code "59") (name "CTRL_CLK") (class "Default")
      (node (ref "U3") (pin "90") (pinfunction "PB4_90") (pintype "bidirectional"))
      (node (ref "U6") (pin "P22") (pinfunction "IO_L42P_GCLK25_TRDY2_3_P22") (pintype "bidirectional"))
    )
    (net (code "60") (name "D0") (class "Default")
      (node (ref "4A") (pin "1") (pinfunction "P_1") (pintype "passive"))
      (node (ref "U2") (pin "13") (pinfunction "DQ0_13") (pintype "output"))
      (node (ref "U6") (pin "P23") (pinfunction "IO_L41N_GCLK26_3_P23") (pintype "bidirectional"))
    )
    (net (code "61") (name "D1") (class "Default")
      (node (ref "5A") (pin "1") (pinfunction "P_1") (pintype "passive"))
      (node (ref "U2") (pin "14") (pinfunction "DQ1_14") (pintype "output"))
      (node (ref "U6") (pin "P26") (pinfunction "IO_L37N_3_P26") (pintype "bidirectional"))
    )
    (net (code "62") (name "D2") (class "Default")
      (node (ref "6A") (pin "1") (pinfunction "P_1") (pintype "passive"))
      (node (ref "U2") (pin "15") (pinfunction "DQ2_15") (pintype "output"))
      (node (ref "U6") (pin "P27") (pinfunction "IO_L37P_3_P27") (pintype "bidirectional"))
    )
    (net (code "63") (name "D3") (class "Default")
      (node (ref "9A") (pin "1") (pinfunction "P_1") (pintype "passive"))
      (node (ref "U2") (pin "17") (pinfunction "DQ3_17") (pintype "output"))
      (node (ref "U6") (pin "P34") (pinfunction "IO_L1N_VREF_3_P34") (pintype "bidirectional"))
    )
    (net (code "64") (name "D4") (class "Default")
      (node (ref "10A") (pin "1") (pinfunction "P_1") (pintype "passive"))
      (node (ref "U2") (pin "18") (pinfunction "DQ4_18") (pintype "output"))
      (node (ref "U6") (pin "P39") (pinfunction "IO_L65P_INIT_B_2_P39") (pintype "bidirectional"))
    )
    (net (code "65") (name "D5") (class "Default")
      (node (ref "8A") (pin "1") (pinfunction "P_1") (pintype "passive"))
      (node (ref "U2") (pin "19") (pinfunction "DQ5_19") (pintype "output"))
      (node (ref "U6") (pin "P32") (pinfunction "IO_L2N_3_P32") (pintype "bidirectional"))
    )
    (net (code "66") (name "D6") (class "Default")
      (node (ref "7A") (pin "1") (pinfunction "P_1") (pintype "passive"))
      (node (ref "U2") (pin "20") (pinfunction "DQ6_20") (pintype "output"))
      (node (ref "U6") (pin "P29") (pinfunction "IO_L36N_3_P29") (pintype "bidirectional"))
    )
    (net (code "67") (name "D7") (class "Default")
      (node (ref "1A") (pin "1") (pinfunction "P_1") (pintype "passive"))
      (node (ref "U2") (pin "21") (pinfunction "DQ7_21") (pintype "output"))
      (node (ref "U6") (pin "P21") (pinfunction "IO_L42N_GCLK24_3_P21") (pintype "bidirectional"))
    )
    (net (code "68") (name "DEBUG_CLOCK") (class "Default")
      (node (ref "R40") (pin "1") (pinfunction "1_1") (pintype "passive"))
      (node (ref "U3") (pin "24") (pinfunction "PA1_24") (pintype "bidirectional"))
      (node (ref "U6") (pin "P144") (pinfunction "IO_L1P_HSWAPEN_0_P144") (pintype "bidirectional"))
    )
    (net (code "69") (name "DEBUG_RDY") (class "Default")
      (node (ref "SJ3") (pin "1") (pinfunction "1_1") (pintype "passive"))
      (node (ref "U3") (pin "25") (pinfunction "PA2_25") (pintype "bidirectional"))
    )
    (net (code "70") (name "DIN") (class "Default")
      (node (ref "U1") (pin "14") (pinfunction "DIN_14") (pintype "input"))
      (node (ref "U6") (pin "P141") (pinfunction "IO_L2N_0_P141") (pintype "bidirectional"))
    )
    (net (code "71") (name "DI_LLS") (class "Default")
      (node (ref "MICRO_SD1") (pin "3") (pinfunction "CMD_3") (pintype "bidirectional"))
      (node (ref "R17") (pin "2") (pinfunction "2_2") (pintype "passive"))
    )
    (net (code "72") (name "DOWN") (class "Default")
      (node (ref "J2") (pin "2") (pinfunction "2_2") (pintype "passive"))
      (node (ref "U6") (pin "P79") (pinfunction "IO_L47P_1_P79") (pintype "bidirectional"))
    )
    (net (code "73") (name "FIRE") (class "Default")
      (node (ref "J2") (pin "6") (pinfunction "6_6") (pintype "passive"))
      (node (ref "U6") (pin "P82") (pinfunction "IO_L45N_1_P82") (pintype "bidirectional"))
    )
    (net (code "74") (name "FLASH_CS") (class "Default")
      (node (ref "U3") (pin "33") (pinfunction "PC4_33") (pintype "bidirectional"))
      (node (ref "U4") (pin "1") (pinfunction "CS_1") (pintype "bidirectional"))
      (node (ref "U6") (pin "P38") (pinfunction "IO_L65N_CSO_B_2_P38") (pintype "bidirectional"))
    )
    (net (code "75") (name "FLASH_MISO") (class "Default")
      (node (ref "U3") (pin "17") (pinfunction "PC2_17") (pintype "bidirectional"))
      (node (ref "U4") (pin "2") (pinfunction "MISO_2") (pintype "bidirectional"))
      (node (ref "U6") (pin "P65") (pinfunction "IO_L3P_D0_DIN_MISO_MISO1_2_P65") (pintype "bidirectional"))
    )
    (net (code "76") (name "FLASH_MOSI") (class "Default")
      (node (ref "U3") (pin "18") (pinfunction "PC3_18") (pintype "bidirectional"))
      (node (ref "U4") (pin "5") (pinfunction "MOSI_5") (pintype "bidirectional"))
      (node (ref "U6") (pin "P64") (pinfunction "IO_L3N_MOSI_CSI_B_MISO0_2_P64") (pintype "bidirectional"))
    )
    (net (code "77") (name "FLASH_SCLK") (class "Default")
      (node (ref "U3") (pin "47") (pinfunction "PB10_47") (pintype "bidirectional"))
      (node (ref "U4") (pin "6") (pinfunction "SCK_6") (pintype "bidirectional"))
      (node (ref "U6") (pin "P70") (pinfunction "IO_L1P_CCLK_2_P70") (pintype "bidirectional"))
    )
    (net (code "78") (name "FPGAPROG") (class "Default")
      (node (ref "U3") (pin "80") (pinfunction "PC12_80") (pintype "bidirectional"))
      (node (ref "U6") (pin "P37") (pinfunction "PROGRAM_B_2_P37") (pintype "bidirectional"))
    )
    (net (code "79") (name "FPGA_DONE") (class "Default")
      (node (ref "U3") (pin "34") (pinfunction "PC5_34") (pintype "bidirectional"))
      (node (ref "U6") (pin "P71") (pinfunction "DONE_2_P71") (pintype "bidirectional"))
    )
    (net (code "80") (name "GET_CTRL_REG") (class "Default")
      (node (ref "U3") (pin "66") (pinfunction "PC9_66") (pintype "bidirectional"))
      (node (ref "U6") (pin "P56") (pinfunction "IO_L30P_GCLK1_D13_2_P56") (pintype "bidirectional"))
    )
    (net (code "81") (name "GET_DATA_REG") (class "Default")
      (node (ref "U3") (pin "78") (pinfunction "PC10_78") (pintype "bidirectional"))
      (node (ref "U6") (pin "P2") (pinfunction "IO_L83P_3_P2") (pintype "bidirectional"))
    )
    (net (code "82") (name "GND") (class "Default")
      (node (ref "4B") (pin "1") (pinfunction "P_1") (pintype "passive"))
      (node (ref "5B") (pin "1") (pinfunction "P_1") (pintype "passive"))
      (node (ref "BT1") (pin "N") (pinfunction "NEG_N") (pintype "passive"))
      (node (ref "C10") (pin "2") (pinfunction "2_2") (pintype "passive"))
      (node (ref "C11") (pin "1") (pinfunction "1_1") (pintype "passive"))
      (node (ref "C12") (pin "1") (pinfunction "1_1") (pintype "passive"))
      (node (ref "C13") (pin "1") (pinfunction "1_1") (pintype "passive"))
      (node (ref "C15") (pin "1") (pinfunction "1_1") (pintype "passive"))
      (node (ref "C16") (pin "1") (pinfunction "1_1") (pintype "passive"))
      (node (ref "C17") (pin "1") (pinfunction "1_1") (pintype "passive"))
      (node (ref "C18") (pin "2") (pinfunction "2_2") (pintype "passive"))
      (node (ref "C19") (pin "2") (pinfunction "2_2") (pintype "passive"))
      (node (ref "C2") (pin "2") (pinfunction "2_2") (pintype "passive"))
      (node (ref "C20") (pin "1") (pinfunction "1_1") (pintype "passive"))
      (node (ref "C21") (pin "1") (pinfunction "1_1") (pintype "passive"))
      (node (ref "C22") (pin "1") (pinfunction "1_1") (pintype "passive"))
      (node (ref "C23") (pin "1") (pinfunction "1_1") (pintype "passive"))
      (node (ref "C24") (pin "2") (pinfunction "2_2") (pintype "passive"))
      (node (ref "C25") (pin "2") (pinfunction "2_2") (pintype "passive"))
      (node (ref "C26") (pin "2") (pinfunction "2_2") (pintype "passive"))
      (node (ref "C3") (pin "2") (pinfunction "2_2") (pintype "passive"))
      (node (ref "C33") (pin "2") (pinfunction "2_2") (pintype "passive"))
      (node (ref "C4") (pin "1") (pinfunction "1_1") (pintype "passive"))
      (node (ref "C5") (pin "1") (pinfunction "1_1") (pintype "passive"))
      (node (ref "C6") (pin "2") (pinfunction "2_2") (pintype "passive"))
      (node (ref "C7") (pin "2") (pinfunction "2_2") (pintype "passive"))
      (node (ref "IC2") (pin "1") (pinfunction "GND_1") (pintype "power_in"))
      (node (ref "IC3") (pin "19") (pinfunction "G_19") (pintype "input"))
      (node (ref "IC5") (pin "1") (pinfunction "GND_1") (pintype "power_in"))
      (node (ref "J2") (pin "8") (pinfunction "8_8") (pintype "passive"))
      (node (ref "J3") (pin "A1_B12") (pinfunction "GND_A1_B12") (pintype "power_in"))
      (node (ref "J3") (pin "B1_A12") (pinfunction "GND_B1_A12") (pintype "power_in"))
      (node (ref "J3") (pin "SH1") (pinfunction "SHIELD_SH1") (pintype "passive"))
      (node (ref "J3") (pin "SH2") (pinfunction "SHIELD_SH2") (pintype "passive"))
      (node (ref "J3") (pin "SH3") (pinfunction "SHIELD_SH3") (pintype "passive"))
      (node (ref "J3") (pin "SH4") (pinfunction "SHIELD_SH4") (pintype "passive"))
      (node (ref "JP4") (pin "2") (pinfunction "2_2") (pintype "passive"))
      (node (ref "JP5") (pin "2") (pinfunction "2_2") (pintype "passive"))
      (node (ref "JP6") (pin "1") (pinfunction "1_1") (pintype "passive"))
      (node (ref "JP8") (pin "2") (pinfunction "2_2") (pintype "passive"))
      (node (ref "LED3") (pin "P1") (pinfunction "C_P1") (pintype "passive"))
      (node (ref "LED3") (pin "P2") (pinfunction "C_P2") (pintype "passive"))
      (node (ref "LED3") (pin "P3") (pinfunction "C_P3") (pintype "passive"))
      (node (ref "MICRO_SD1") (pin "6") (pinfunction "VSS_6") (pintype "power_in"))
      (node (ref "MICRO_SD1") (pin "MP1") (pinfunction "SHIELD_MP1") (pintype "power_in"))
      (node (ref "MICRO_SD1") (pin "MP2") (pinfunction "SHIELD_MP2") (pintype "power_in"))
      (node (ref "MICRO_SD1") (pin "MP3") (pinfunction "SHIELD_MP3") (pintype "power_in"))
      (node (ref "MICRO_SD1") (pin "MP4") (pinfunction "SHIELD_MP4") (pintype "power_in"))
      (node (ref "Q1") (pin "2") (pinfunction "GND_2") (pintype "power_in"))
      (node (ref "R19") (pin "2") (pinfunction "2_2") (pintype "passive"))
      (node (ref "R25") (pin "1") (pinfunction "1_1") (pintype "passive"))
      (node (ref "R27") (pin "2") (pinfunction "2_2") (pintype "passive"))
      (node (ref "R28") (pin "2") (pinfunction "2_2") (pintype "passive"))
      (node (ref "R30") (pin "1") (pinfunction "1_1") (pintype "passive"))
      (node (ref "R38") (pin "2") (pinfunction "2_2") (pintype "passive"))
      (node (ref "R40") (pin "2") (pinfunction "2_2") (pintype "passive"))
      (node (ref "S1") (pin "1") (pinfunction "P_1") (pintype "passive"))
      (node (ref "S2") (pin "1") (pinfunction "P_1") (pintype "passive"))
      (node (ref "U1") (pin "10") (pinfunction "DEMP_10") (pintype "bidirectional"))
      (node (ref "U1") (pin "11") (pinfunction "FLT_11") (pintype "bidirectional"))
      (node (ref "U1") (pin "12") (pinfunction "SCK_12") (pintype "bidirectional"))
      (node (ref "U1") (pin "16") (pinfunction "FMT_16") (pintype "bidirectional"))
      (node (ref "U1") (pin "19") (pinfunction "DGND_19") (pintype "power_in"))
      (node (ref "U1") (pin "3") (pinfunction "CPGND_3") (pintype "power_in"))
      (node (ref "U1") (pin "9") (pinfunction "AGND_9") (pintype "power_in"))
      (node (ref "U2") (pin "16") (pinfunction "VSS_16") (pintype "output"))
      (node (ref "U2") (pin "22") (pinfunction "CE_22") (pintype "input"))
      (node (ref "U3") (pin "10") (pinfunction "VSS_10") (pintype "bidirectional"))
      (node (ref "U3") (pin "20") (pinfunction "VSSA_20") (pintype "bidirectional"))
      (node (ref "U3") (pin "27") (pinfunction "VSS_27") (pintype "bidirectional"))
      (node (ref "U3") (pin "74") (pinfunction "VSS_74") (pintype "bidirectional"))
      (node (ref "U3") (pin "99") (pinfunction "VSS_99") (pintype "bidirectional"))
      (node (ref "U4") (pin "4") (pinfunction "GND_4") (pintype "power_in"))
      (node (ref "U6") (pin "P108") (pinfunction "GND_P108") (pintype "bidirectional"))
      (node (ref "U6") (pin "P113") (pinfunction "GND_P113") (pintype "bidirectional"))
      (node (ref "U6") (pin "P13") (pinfunction "GND_P13") (pintype "bidirectional"))
      (node (ref "U6") (pin "P130") (pinfunction "GND_P130") (pintype "bidirectional"))
      (node (ref "U6") (pin "P136") (pinfunction "GND_P136") (pintype "bidirectional"))
      (node (ref "U6") (pin "P25") (pinfunction "GND_P25") (pintype "bidirectional"))
      (node (ref "U6") (pin "P3") (pinfunction "GND_P3") (pintype "bidirectional"))
      (node (ref "U6") (pin "P49") (pinfunction "GND_P49") (pintype "bidirectional"))
      (node (ref "U6") (pin "P54") (pinfunction "GND_P54") (pintype "bidirectional"))
      (node (ref "U6") (pin "P68") (pinfunction "GND_P68") (pintype "bidirectional"))
      (node (ref "U6") (pin "P73") (pinfunction "SUSPEND_P73") (pintype "bidirectional"))
      (node (ref "U6") (pin "P77") (pinfunction "GND_P77") (pintype "bidirectional"))
      (node (ref "U6") (pin "P91") (pinfunction "GND_P91") (pintype "bidirectional"))
      (node (ref "U6") (pin "P96") (pinfunction "GND_P96") (pintype "bidirectional"))
      (node (ref "X1") (pin "13") (pinfunction "13_13") (pintype "passive"))
      (node (ref "X1") (pin "14") (pinfunction "14_14") (pintype "passive"))
      (node (ref "X1") (pin "17") (pinfunction "17_17") (pintype "passive"))
      (node (ref "X1") (pin "18") (pinfunction "18_18") (pintype "passive"))
      (node (ref "X1") (pin "21") (pinfunction "21_21") (pintype "passive"))
      (node (ref "X1") (pin "4") (pinfunction "4_4") (pintype "passive"))
      (node (ref "X1") (pin "5") (pinfunction "5_5") (pintype "passive"))
      (node (ref "X1") (pin "8") (pinfunction "8_8") (pintype "passive"))
      (node (ref "X1") (pin "9") (pinfunction "9_9") (pintype "passive"))
    )
    (net (code "83") (name "LEDB") (class "Default")
      (node (ref "R3") (pin "1") (pinfunction "1_1") (pintype "passive"))
      (node (ref "U3") (pin "64") (pinfunction "PC7_64") (pintype "bidirectional"))
    )
    (net (code "84") (name "LEDG") (class "Default")
      (node (ref "R13") (pin "1") (pinfunction "1_1") (pintype "passive"))
      (node (ref "U3") (pin "63") (pinfunction "PC6_63") (pintype "bidirectional"))
    )
    (net (code "85") (name "LEDR") (class "Default")
      (node (ref "R2") (pin "1") (pinfunction "1_1") (pintype "passive"))
      (node (ref "U3") (pin "65") (pinfunction "PC8_65") (pintype "bidirectional"))
    )
    (net (code "86") (name "LEFT") (class "Default")
      (node (ref "J2") (pin "3") (pinfunction "3_3") (pintype "passive"))
      (node (ref "U6") (pin "P80") (pinfunction "IO_L46N_1_P80") (pintype "bidirectional"))
    )
    (net (code "87") (name "LRCK") (class "Default")
      (node (ref "U1") (pin "15") (pinfunction "LRCK_15") (pintype "bidirectional"))
      (node (ref "U6") (pin "P134") (pinfunction "IO_L34P_GCLK19_0_P134") (pintype "bidirectional"))
    )
    (net (code "88") (name "MISO") (class "Default")
      (node (ref "R20") (pin "1") (pinfunction "1_1") (pintype "passive"))
      (node (ref "U3") (pin "31") (pinfunction "PA6_31") (pintype "bidirectional"))
    )
    (net (code "89") (name "MOSI") (class "Default")
      (node (ref "R17") (pin "1") (pinfunction "1_1") (pintype "passive"))
      (node (ref "U3") (pin "32") (pinfunction "PA7_32") (pintype "bidirectional"))
    )
    (net (code "90") (name "Net-(1B-P)") (class "Default")
      (node (ref "1B") (pin "1") (pinfunction "P_1") (pintype "passive"))
      (node (ref "D4") (pin "A") (pinfunction "A_A") (pintype "passive"))
    )
    (net (code "91") (name "Net-(BT1-POS)") (class "Default")
      (node (ref "BT1") (pin "P") (pinfunction "POS_P") (pintype "passive"))
      (node (ref "D3") (pin "2") (pinfunction "A2_2") (pintype "passive"))
      (node (ref "U3") (pin "16") (pinfunction "PC1_16") (pintype "bidirectional"))
    )
    (net (code "92") (name "Net-(C1-Pad-)") (class "Default")
      (node (ref "C1") (pin "-") (pinfunction "-_-") (pintype "passive"))
      (node (ref "R4") (pin "2") (pinfunction "2_2") (pintype "passive"))
    )
    (net (code "93") (name "Net-(C9-Pad1)") (class "Default")
      (node (ref "C9") (pin "1") (pinfunction "1_1") (pintype "passive"))
      (node (ref "R1") (pin "2") (pinfunction "2_2") (pintype "passive"))
      (node (ref "R5") (pin "2") (pinfunction "2_2") (pintype "passive"))
    )
    (net (code "94") (name "Net-(C20-Pad2)") (class "Default")
      (node (ref "C20") (pin "2") (pinfunction "2_2") (pintype "passive"))
      (node (ref "R37") (pin "1") (pinfunction "1_1") (pintype "passive"))
      (node (ref "R9") (pin "1") (pinfunction "1_1") (pintype "passive"))
    )
    (net (code "95") (name "Net-(C21-Pad2)") (class "Default")
      (node (ref "C21") (pin "2") (pinfunction "2_2") (pintype "passive"))
      (node (ref "R10") (pin "1") (pinfunction "1_1") (pintype "passive"))
      (node (ref "R8") (pin "1") (pinfunction "1_1") (pintype "passive"))
    )
    (net (code "96") (name "Net-(D3-CC)") (class "Default")
      (node (ref "D3") (pin "3") (pinfunction "CC_3") (pintype "passive"))
      (node (ref "U3") (pin "6") (pinfunction "VBAT_6") (pintype "bidirectional"))
    )
    (net (code "97") (name "Net-(J3-DN1)") (class "Default")
      (node (ref "J3") (pin "A7") (pinfunction "DN1_A7") (pintype "bidirectional"))
      (node (ref "J3") (pin "B7") (pinfunction "DN2_B7") (pintype "bidirectional"))
      (node (ref "R26") (pin "1") (pinfunction "1_1") (pintype "passive"))
    )
    (net (code "98") (name "Net-(J3-DP1)") (class "Default")
      (node (ref "J3") (pin "A6") (pinfunction "DP1_A6") (pintype "bidirectional"))
      (node (ref "J3") (pin "B6") (pinfunction "DP2_B6") (pintype "bidirectional"))
      (node (ref "R22") (pin "1") (pinfunction "1_1") (pintype "passive"))
      (node (ref "R23") (pin "1") (pinfunction "1_1") (pintype "passive"))
    )
    (net (code "99") (name "Net-(JP2-Pad1)") (class "Default")
      (node (ref "JP2") (pin "1") (pinfunction "1_1") (pintype "passive"))
      (node (ref "X1") (pin "16") (pinfunction "16_16") (pintype "passive"))
    )
    (net (code "100") (name "Net-(JP2-Pad2)") (class "Default")
      (node (ref "JP2") (pin "2") (pinfunction "2_2") (pintype "passive"))
      (node (ref "R36") (pin "1") (pinfunction "1_1") (pintype "passive"))
    )
    (net (code "101") (name "Net-(JP7-Pad1)") (class "Default")
      (node (ref "JP7") (pin "1") (pinfunction "1_1") (pintype "passive"))
      (node (ref "R24") (pin "2") (pinfunction "2_2") (pintype "passive"))
    )
    (net (code "102") (name "Net-(JP7-Pad3)") (class "Default")
      (node (ref "JP7") (pin "3") (pinfunction "3_3") (pintype "passive"))
      (node (ref "R16") (pin "1") (pinfunction "1_1") (pintype "passive"))
    )
    (net (code "103") (name "Net-(LED2-PadA)") (class "Default")
      (node (ref "LED2") (pin "A") (pinfunction "A_A") (pintype "passive"))
      (node (ref "R11") (pin "2") (pinfunction "2_2") (pintype "passive"))
    )
    (net (code "104") (name "Net-(LED3A-A)") (class "Default")
      (node (ref "LED3") (pin "P6") (pinfunction "A_P6") (pintype "passive"))
      (node (ref "R3") (pin "2") (pinfunction "2_2") (pintype "passive"))
    )
    (net (code "105") (name "Net-(LED3B-A)") (class "Default")
      (node (ref "LED3") (pin "P5") (pinfunction "A_P5") (pintype "passive"))
      (node (ref "R13") (pin "2") (pinfunction "2_2") (pintype "passive"))
    )
    (net (code "106") (name "Net-(LED3C-A)") (class "Default")
      (node (ref "LED3") (pin "P4") (pinfunction "A_P4") (pintype "passive"))
      (node (ref "R2") (pin "2") (pinfunction "2_2") (pintype "passive"))
    )
    (net (code "107") (name "Net-(MICRO_SD1-DAT0)") (class "Default")
      (node (ref "MICRO_SD1") (pin "7") (pinfunction "DAT0_7") (pintype "bidirectional"))
      (node (ref "R20") (pin "2") (pinfunction "2_2") (pintype "passive"))
    )
    (net (code "108") (name "Net-(Q3-2)") (class "Default")
      (node (ref "C12") (pin "2") (pinfunction "2_2") (pintype "passive"))
      (node (ref "Q3") (pin "3") (pinfunction "2_3") (pintype "passive"))
      (node (ref "R14") (pin "2") (pinfunction "2_2") (pintype "passive"))
      (node (ref "U3") (pin "13") (pinfunction "PH1_13") (pintype "bidirectional"))
    )
    (net (code "109") (name "Net-(R1-Pad1)") (class "Default")
      (node (ref "R1") (pin "1") (pinfunction "1_1") (pintype "passive"))
      (node (ref "R37") (pin "2") (pinfunction "2_2") (pintype "passive"))
      (node (ref "X1") (pin "1") (pinfunction "1_1") (pintype "passive"))
    )
    (net (code "110") (name "Net-(R10-Pad2)") (class "Default")
      (node (ref "R10") (pin "2") (pinfunction "2_2") (pintype "passive"))
      (node (ref "R5") (pin "1") (pinfunction "1_1") (pintype "passive"))
      (node (ref "X1") (pin "3") (pinfunction "3_3") (pintype "passive"))
    )
    (net (code "111") (name "Net-(S2-S)") (class "Default")
      (node (ref "C13") (pin "2") (pinfunction "2_2") (pintype "passive"))
      (node (ref "R6") (pin "1") (pinfunction "1_1") (pintype "passive"))
      (node (ref "S2") (pin "2") (pinfunction "S_2") (pintype "passive"))
      (node (ref "U3") (pin "79") (pinfunction "PC11_79") (pintype "bidirectional"))
    )
    (net (code "112") (name "Net-(U1-CAMP)") (class "Default")
      (node (ref "C8") (pin "1") (pinfunction "1_1") (pintype "passive"))
      (node (ref "U1") (pin "4") (pinfunction "CAMP_4") (pintype "bidirectional"))
    )
    (net (code "113") (name "Net-(U1-CAPP)") (class "Default")
      (node (ref "C8") (pin "2") (pinfunction "2_2") (pintype "passive"))
      (node (ref "U1") (pin "2") (pinfunction "CAPP_2") (pintype "bidirectional"))
    )
    (net (code "114") (name "Net-(U1-LDOO)") (class "Default")
      (node (ref "C17") (pin "2") (pinfunction "2_2") (pintype "passive"))
      (node (ref "U1") (pin "18") (pinfunction "LDOO_18") (pintype "bidirectional"))
    )
    (net (code "115") (name "Net-(U1-OUTL)") (class "Default")
      (node (ref "R8") (pin "2") (pinfunction "2_2") (pintype "passive"))
      (node (ref "U1") (pin "6") (pinfunction "OUTL_6") (pintype "output"))
    )
    (net (code "116") (name "Net-(U1-OUTR)") (class "Default")
      (node (ref "R9") (pin "2") (pinfunction "2_2") (pintype "passive"))
      (node (ref "U1") (pin "7") (pinfunction "OUTR_7") (pintype "output"))
    )
    (net (code "117") (name "Net-(U1-VNEG)") (class "Default")
      (node (ref "C15") (pin "2") (pinfunction "2_2") (pintype "passive"))
      (node (ref "U1") (pin "5") (pinfunction "VNEG_5") (pintype "bidirectional"))
    )
    (net (code "118") (name "Net-(U3-PC14)") (class "Default")
      (node (ref "C22") (pin "2") (pinfunction "2_2") (pintype "passive"))
      (node (ref "Q4") (pin "2") (pinfunction "2_2") (pintype "passive"))
      (node (ref "U3") (pin "8") (pinfunction "PC14_8") (pintype "bidirectional"))
    )
    (net (code "119") (name "Net-(U3-PC15)") (class "Default")
      (node (ref "C23") (pin "2") (pinfunction "2_2") (pintype "passive"))
      (node (ref "Q4") (pin "1") (pinfunction "1_1") (pintype "passive"))
      (node (ref "U3") (pin "9") (pinfunction "PC15_9") (pintype "bidirectional"))
    )
    (net (code "120") (name "Net-(U3-PH0)") (class "Default")
      (node (ref "C11") (pin "2") (pinfunction "2_2") (pintype "passive"))
      (node (ref "Q3") (pin "1") (pinfunction "1_1") (pintype "passive"))
      (node (ref "R14") (pin "1") (pinfunction "1_1") (pintype "passive"))
      (node (ref "U3") (pin "12") (pinfunction "PH0_12") (pintype "bidirectional"))
    )
    (net (code "121") (name "Net-(U3-VCAP_1)") (class "Default")
      (node (ref "C10") (pin "1") (pinfunction "1_1") (pintype "passive"))
      (node (ref "U3") (pin "49") (pinfunction "VCAP_1_49") (pintype "bidirectional"))
    )
    (net (code "122") (name "Net-(U3-VCAP_2)") (class "Default")
      (node (ref "C7") (pin "1") (pinfunction "1_1") (pintype "passive"))
      (node (ref "U3") (pin "73") (pinfunction "VCAP_2_73") (pintype "bidirectional"))
    )
    (net (code "123") (name "Net-(U6-IO_L1N_M0_CMPMISO_2)") (class "Default")
      (node (ref "R39") (pin "2") (pinfunction "2_2") (pintype "passive"))
      (node (ref "SJ4") (pin "1") (pinfunction "1_1") (pintype "passive"))
      (node (ref "U6") (pin "P69") (pinfunction "IO_L1N_M0_CMPMISO_2_P69") (pintype "bidirectional"))
    )
    (net (code "124") (name "Net-(U6-IO_L13P_M1_2)") (class "Default")
      (node (ref "R38") (pin "1") (pinfunction "1_1") (pintype "passive"))
      (node (ref "SJ3") (pin "2") (pinfunction "2_2") (pintype "passive"))
      (node (ref "U6") (pin "P60") (pinfunction "IO_L13P_M1_2_P60") (pintype "bidirectional"))
    )
    (net (code "125") (name "O0") (class "Default")
      (node (ref "U3") (pin "81") (pinfunction "PD0_81") (pintype "bidirectional"))
      (node (ref "U6") (pin "P126") (pinfunction "IO_L36N_GCLK14_0_P126") (pintype "bidirectional"))
    )
    (net (code "126") (name "O1") (class "Default")
      (node (ref "U3") (pin "82") (pinfunction "PD1_82") (pintype "bidirectional"))
      (node (ref "U6") (pin "P127") (pinfunction "IO_L36P_GCLK15_0_P127") (pintype "bidirectional"))
    )
    (net (code "127") (name "O2") (class "Default")
      (node (ref "U3") (pin "83") (pinfunction "PD2_83") (pintype "bidirectional"))
      (node (ref "U6") (pin "P131") (pinfunction "IO_L35N_GCLK16_0_P131") (pintype "bidirectional"))
    )
    (net (code "128") (name "O3") (class "Default")
      (node (ref "U3") (pin "84") (pinfunction "PD3_84") (pintype "bidirectional"))
      (node (ref "U6") (pin "P132") (pinfunction "IO_L35P_GCLK17_0_P132") (pintype "bidirectional"))
    )
    (net (code "129") (name "O4") (class "Default")
      (node (ref "U3") (pin "85") (pinfunction "PD4_85") (pintype "bidirectional"))
      (node (ref "U6") (pin "P133") (pinfunction "IO_L34N_GCLK18_0_P133") (pintype "bidirectional"))
    )
    (net (code "130") (name "O5") (class "Default")
      (node (ref "U3") (pin "86") (pinfunction "PD5_86") (pintype "bidirectional"))
      (node (ref "U6") (pin "P137") (pinfunction "IO_L4N_0_P137") (pintype "bidirectional"))
    )
    (net (code "131") (name "O6") (class "Default")
      (node (ref "U3") (pin "87") (pinfunction "PD6_87") (pintype "bidirectional"))
      (node (ref "U6") (pin "P138") (pinfunction "IO_L4P_0_P138") (pintype "bidirectional"))
    )
    (net (code "132") (name "O7") (class "Default")
      (node (ref "U3") (pin "88") (pinfunction "PD7_88") (pintype "bidirectional"))
      (node (ref "U6") (pin "P139") (pinfunction "IO_L3N_0_P139") (pintype "bidirectional"))
    )
    (net (code "133") (name "PA11{slash}USB_DN") (class "Default")
      (node (ref "R26") (pin "2") (pinfunction "2_2") (pintype "passive"))
      (node (ref "U3") (pin "70") (pinfunction "PA11_70") (pintype "bidirectional"))
    )
    (net (code "134") (name "PA12{slash}USB_DP") (class "Default")
      (node (ref "R23") (pin "2") (pinfunction "2_2") (pintype "passive"))
      (node (ref "U3") (pin "71") (pinfunction "PA12_71") (pintype "bidirectional"))
    )
    (net (code "135") (name "PA13{slash}JTMS{slash}SWDIO") (class "Default")
      (node (ref "JP8") (pin "1") (pinfunction "1_1") (pintype "passive"))
      (node (ref "U3") (pin "72") (pinfunction "PA13_72") (pintype "bidirectional"))
    )
    (net (code "136") (name "PA14{slash}JTCK{slash}SWCLK") (class "Default")
      (node (ref "JP8") (pin "3") (pinfunction "3_3") (pintype "passive"))
      (node (ref "U3") (pin "76") (pinfunction "PA14_76") (pintype "bidirectional"))
    )
    (net (code "137") (name "PB2{slash}BOOT1") (class "Default")
      (node (ref "R16") (pin "2") (pinfunction "2_2") (pintype "passive"))
      (node (ref "R25") (pin "2") (pinfunction "2_2") (pintype "passive"))
      (node (ref "U3") (pin "37") (pinfunction "PB2_37") (pintype "bidirectional"))
    )
    (net (code "138") (name "RIGHT") (class "Default")
      (node (ref "J2") (pin "4") (pinfunction "4_4") (pintype "passive"))
      (node (ref "U6") (pin "P81") (pinfunction "IO_L46P_1_P81") (pintype "bidirectional"))
    )
    (net (code "139") (name "RST_CTRL_REG") (class "Default")
      (node (ref "U3") (pin "53") (pinfunction "PB14_53") (pintype "bidirectional"))
      (node (ref "U6") (pin "P1") (pinfunction "IO_L83N_VREF_3_P1") (pintype "bidirectional"))
    )
    (net (code "140") (name "RST_DATA_REG") (class "Default")
      (node (ref "U3") (pin "91") (pinfunction "PB5_91") (pintype "bidirectional"))
      (node (ref "U6") (pin "P142") (pinfunction "IO_L2P_0_P142") (pintype "bidirectional"))
    )
    (net (code "141") (name "SCK_LLS") (class "Default")
      (node (ref "MICRO_SD1") (pin "5") (pinfunction "CLK_5") (pintype "bidirectional"))
      (node (ref "R18") (pin "2") (pinfunction "2_2") (pintype "passive"))
    )
    (net (code "142") (name "SCL") (class "Default")
      (node (ref "JP6") (pin "3") (pinfunction "3_3") (pintype "passive"))
      (node (ref "U3") (pin "92") (pinfunction "PB6_92") (pintype "bidirectional"))
    )
    (net (code "143") (name "SCLK") (class "Default")
      (node (ref "R18") (pin "1") (pinfunction "1_1") (pintype "passive"))
      (node (ref "U3") (pin "30") (pinfunction "PA5_30") (pintype "bidirectional"))
    )
    (net (code "144") (name "SDA") (class "Default")
      (node (ref "JP6") (pin "2") (pinfunction "2_2") (pintype "passive"))
      (node (ref "U3") (pin "93") (pinfunction "PB7_93") (pintype "bidirectional"))
    )
    (net (code "145") (name "SD_LED") (class "Default")
      (node (ref "LED2") (pin "C") (pinfunction "C_C") (pintype "passive"))
      (node (ref "U3") (pin "15") (pinfunction "PC0_15") (pintype "bidirectional"))
    )
    (net (code "146") (name "SOUND") (class "Default")
      (node (ref "C9") (pin "2") (pinfunction "2_2") (pintype "passive"))
      (node (ref "U3") (pin "29") (pinfunction "PA4_29") (pintype "bidirectional"))
    )
    (net (code "147") (name "SPARE1") (class "Default")
      (node (ref "JP6") (pin "4") (pinfunction "4_4") (pintype "passive"))
      (node (ref "U3") (pin "7") (pinfunction "PC13_7") (pintype "bidirectional"))
    )
    (net (code "148") (name "SS_SD") (class "Default")
      (node (ref "R21") (pin "1") (pinfunction "1_1") (pintype "passive"))
      (node (ref "U3") (pin "54") (pinfunction "PB15_54") (pintype "bidirectional"))
    )
    (net (code "149") (name "TCK") (class "Default")
      (node (ref "JP3") (pin "1") (pinfunction "1_1") (pintype "passive"))
      (node (ref "U6") (pin "P109") (pinfunction "TCK_P109") (pintype "bidirectional"))
    )
    (net (code "150") (name "TDI") (class "Default")
      (node (ref "JP3") (pin "3") (pinfunction "3_3") (pintype "passive"))
      (node (ref "U6") (pin "P110") (pinfunction "TDI_P110") (pintype "bidirectional"))
    )
    (net (code "151") (name "TDO") (class "Default")
      (node (ref "JP3") (pin "2") (pinfunction "2_2") (pintype "passive"))
      (node (ref "U6") (pin "P106") (pinfunction "TDO_P106") (pintype "bidirectional"))
    )
    (net (code "152") (name "TMS") (class "Default")
      (node (ref "JP3") (pin "4") (pinfunction "4_4") (pintype "passive"))
      (node (ref "U6") (pin "P107") (pinfunction "TMS_P107") (pintype "bidirectional"))
    )
    (net (code "153") (name "UART_RX") (class "Default")
      (node (ref "JP4") (pin "3") (pinfunction "3_3") (pintype "passive"))
      (node (ref "U3") (pin "69") (pinfunction "PA10_69") (pintype "bidirectional"))
    )
    (net (code "154") (name "UART_TX") (class "Default")
      (node (ref "JP4") (pin "4") (pinfunction "4_4") (pintype "passive"))
      (node (ref "U3") (pin "68") (pinfunction "PA9_68") (pintype "bidirectional"))
    )
    (net (code "155") (name "UP") (class "Default")
      (node (ref "J2") (pin "1") (pinfunction "1_1") (pintype "passive"))
      (node (ref "U6") (pin "P78") (pinfunction "IO_L47N_1_P78") (pintype "bidirectional"))
    )
    (net (code "156") (name "VCC") (class "Default")
      (node (ref "23B") (pin "1") (pinfunction "P_1") (pintype "passive"))
      (node (ref "2A") (pin "1") (pinfunction "P_1") (pintype "passive"))
      (node (ref "C3") (pin "1") (pinfunction "1_1") (pintype "passive"))
      (node (ref "D2") (pin "C") (pinfunction "C_C") (pintype "passive"))
      (node (ref "D4") (pin "C") (pinfunction "C_C") (pintype "passive"))
      (node (ref "IC2") (pin "3") (pinfunction "VIN_3") (pintype "input"))
      (node (ref "IC3") (pin "1") (pinfunction "DIR_1") (pintype "input"))
      (node (ref "IC5") (pin "3") (pinfunction "VIN_3") (pintype "input"))
      (node (ref "JP4") (pin "1") (pinfunction "1_1") (pintype "passive"))
      (node (ref "R11") (pin "1") (pinfunction "1_1") (pintype "passive"))
      (node (ref "R15") (pin "2") (pinfunction "2_2") (pintype "passive"))
      (node (ref "R22") (pin "2") (pinfunction "2_2") (pintype "passive"))
      (node (ref "R6") (pin "2") (pinfunction "2_2") (pintype "passive"))
      (node (ref "U2") (pin "32") (pinfunction "VCC_32") (pintype "power_in"))
    )
    (net (code "157") (name "VCC_USB") (class "Default")
      (node (ref "D2") (pin "A") (pinfunction "A_A") (pintype "passive"))
      (node (ref "J3") (pin "A4_B9") (pinfunction "VBUS_A4_B9") (pintype "power_in"))
      (node (ref "J3") (pin "B4_A9") (pinfunction "VBUS_B4_A9") (pintype "power_in"))
    )
    (net (code "158") (name "V_BLUE") (class "Default")
      (node (ref "R29") (pin "1") (pinfunction "1_1") (pintype "passive"))
      (node (ref "U6") (pin "P9") (pinfunction "IO_L50N_3_P9") (pintype "bidirectional"))
    )
    (net (code "159") (name "V_BLUE'") (class "Default")
      (node (ref "R28") (pin "1") (pinfunction "1_1") (pintype "passive"))
      (node (ref "R29") (pin "2") (pinfunction "2_2") (pintype "passive"))
      (node (ref "R33") (pin "2") (pinfunction "2_2") (pintype "passive"))
      (node (ref "X1") (pin "7") (pinfunction "7_7") (pintype "passive"))
    )
    (net (code "160") (name "V_GREEN") (class "Default")
      (node (ref "R31") (pin "1") (pinfunction "1_1") (pintype "passive"))
      (node (ref "U6") (pin "P8") (pinfunction "IO_L51P_3_P8") (pintype "bidirectional"))
    )
    (net (code "161") (name "V_GREEN'") (class "Default")
      (node (ref "R27") (pin "1") (pinfunction "1_1") (pintype "passive"))
      (node (ref "R31") (pin "2") (pinfunction "2_2") (pintype "passive"))
      (node (ref "R34") (pin "2") (pinfunction "2_2") (pintype "passive"))
      (node (ref "X1") (pin "11") (pinfunction "11_11") (pintype "passive"))
    )
    (net (code "162") (name "V_RED") (class "Default")
      (node (ref "R32") (pin "1") (pinfunction "1_1") (pintype "passive"))
      (node (ref "U6") (pin "P7") (pinfunction "IO_L51N_3_P7") (pintype "bidirectional"))
    )
    (net (code "163") (name "V_RED'") (class "Default")
      (node (ref "R19") (pin "1") (pinfunction "1_1") (pintype "passive"))
      (node (ref "R32") (pin "2") (pinfunction "2_2") (pintype "passive"))
      (node (ref "R35") (pin "2") (pinfunction "2_2") (pintype "passive"))
      (node (ref "X1") (pin "15") (pinfunction "15_15") (pintype "passive"))
    )
    (net (code "164") (name "unconnected-(IC3A-A7-Pad8)") (class "Default")
      (node (ref "IC3") (pin "8") (pinfunction "A7_8") (pintype "bidirectional"))
    )
    (net (code "165") (name "unconnected-(IC3A-A8-Pad9)") (class "Default")
      (node (ref "IC3") (pin "9") (pinfunction "A8_9") (pintype "bidirectional"))
    )
    (net (code "166") (name "unconnected-(IC3A-B7-Pad12)") (class "Default")
      (node (ref "IC3") (pin "12") (pinfunction "B7_12") (pintype "bidirectional"))
    )
    (net (code "167") (name "unconnected-(IC3A-B8-Pad11)") (class "Default")
      (node (ref "IC3") (pin "11") (pinfunction "B8_11") (pintype "bidirectional"))
    )
    (net (code "168") (name "unconnected-(J2-Pad5)") (class "Default")
      (node (ref "J2") (pin "5") (pinfunction "5_5") (pintype "passive"))
    )
    (net (code "169") (name "unconnected-(J2-Pad7)") (class "Default")
      (node (ref "J2") (pin "7") (pinfunction "7_7") (pintype "passive"))
    )
    (net (code "170") (name "unconnected-(J2-Pad9)") (class "Default")
      (node (ref "J2") (pin "9") (pinfunction "9_9") (pintype "passive"))
    )
    (net (code "171") (name "unconnected-(MICRO_SD1-CD-PadCD1)") (class "Default")
      (node (ref "MICRO_SD1") (pin "CD1") (pinfunction "CD_CD1") (pintype "passive"))
    )
    (net (code "172") (name "unconnected-(MICRO_SD1-DAT1-Pad8)") (class "Default")
      (node (ref "MICRO_SD1") (pin "8") (pinfunction "DAT1_8") (pintype "bidirectional"))
    )
    (net (code "173") (name "unconnected-(MICRO_SD1-DAT2-Pad1)") (class "Default")
      (node (ref "MICRO_SD1") (pin "1") (pinfunction "DAT2_1") (pintype "bidirectional"))
    )
    (net (code "174") (name "unconnected-(Q1-TS-Pad1)") (class "Default")
      (node (ref "Q1") (pin "1") (pinfunction "TS_1") (pintype "passive"))
    )
    (net (code "175") (name "unconnected-(U6-CMPCS_B_2-PadP72)") (class "Default")
      (node (ref "U6") (pin "P72") (pinfunction "CMPCS_B_2_P72") (pintype "bidirectional"))
    )
    (net (code "176") (name "unconnected-(X1-Pad2)") (class "Default")
      (node (ref "X1") (pin "2") (pinfunction "2_2") (pintype "passive"))
    )
    (net (code "177") (name "unconnected-(X1-Pad6)") (class "Default")
      (node (ref "X1") (pin "6") (pinfunction "6_6") (pintype "passive"))
    )
    (net (code "178") (name "unconnected-(X1-Pad10)") (class "Default")
      (node (ref "X1") (pin "10") (pinfunction "10_10") (pintype "passive"))
    )
    (net (code "179") (name "unconnected-(X1-Pad12)") (class "Default")
      (node (ref "X1") (pin "12") (pinfunction "12_12") (pintype "passive"))
    )
    (net (code "180") (name "unconnected-(X1-Pad20)") (class "Default")
      (node (ref "X1") (pin "20") (pinfunction "20_20") (pintype "passive"))
    )
    (net (code "181") (name "{slash}BUSAK") (class "Default")
      (node (ref "18A") (pin "1") (pinfunction "P_1") (pintype "passive"))
      (node (ref "SJ4") (pin "2") (pinfunction "2_2") (pintype "passive"))
    )
    (net (code "182") (name "{slash}BUSRQ") (class "Default")
      (node (ref "20A") (pin "1") (pinfunction "P_1") (pintype "passive"))
      (node (ref "SJ2") (pin "2") (pinfunction "2_2") (pintype "passive"))
    )
    (net (code "183") (name "{slash}BUSRQ'") (class "Default")
      (node (ref "SJ2") (pin "1") (pinfunction "1_1") (pintype "passive"))
      (node (ref "U6") (pin "P75") (pinfunction "IO_L74P_AWAKE_1_P75") (pintype "bidirectional"))
    )
    (net (code "184") (name "{slash}CLOCK") (class "Default")
      (node (ref "6B") (pin "1") (pinfunction "P_1") (pintype "passive"))
      (node (ref "U6") (pin "P24") (pinfunction "IO_L41P_GCLK27_3_P24") (pintype "bidirectional"))
    )
    (net (code "185") (name "{slash}HALT") (class "Default")
      (node (ref "R7") (pin "2") (pinfunction "2_2") (pintype "passive"))
      (node (ref "U6") (pin "P45") (pinfunction "IO_L49N_D4_2_P45") (pintype "bidirectional"))
    )
    (net (code "186") (name "{slash}HALT'") (class "Default")
      (node (ref "13A") (pin "1") (pinfunction "P_1") (pintype "passive"))
      (node (ref "R7") (pin "1") (pinfunction "1_1") (pintype "passive"))
    )
    (net (code "187") (name "{slash}IORQ") (class "Default")
      (node (ref "IC3") (pin "14") (pinfunction "B5_14") (pintype "bidirectional"))
      (node (ref "U6") (pin "P51") (pinfunction "IO_L31P_GCLK31_D14_2_P51") (pintype "bidirectional"))
    )
    (net (code "188") (name "{slash}IORQ_5") (class "Default")
      (node (ref "15A") (pin "1") (pinfunction "P_1") (pintype "passive"))
      (node (ref "IC3") (pin "6") (pinfunction "A5_6") (pintype "bidirectional"))
      (node (ref "U6") (pin "P143") (pinfunction "IO_L1N_VREF_0_P143") (pintype "bidirectional"))
    )
    (net (code "189") (name "{slash}M1") (class "Default")
      (node (ref "IC3") (pin "17") (pinfunction "B2_17") (pintype "bidirectional"))
      (node (ref "U6") (pin "P67") (pinfunction "IO_L2P_CMPCLK_2_P67") (pintype "bidirectional"))
    )
    (net (code "190") (name "{slash}M1_5") (class "Default")
      (node (ref "22A") (pin "1") (pinfunction "P_1") (pintype "passive"))
      (node (ref "IC3") (pin "3") (pinfunction "A2_3") (pintype "bidirectional"))
    )
    (net (code "191") (name "{slash}MEM_OE") (class "Default")
      (node (ref "U2") (pin "24") (pinfunction "OE_24") (pintype "input"))
      (node (ref "U3") (pin "67") (pinfunction "PA8_67") (pintype "bidirectional"))
      (node (ref "U6") (pin "P92") (pinfunction "IO_L41N_GCLK8_1_P92") (pintype "bidirectional"))
    )
    (net (code "192") (name "{slash}MREQ") (class "Default")
      (node (ref "IC3") (pin "13") (pinfunction "B6_13") (pintype "bidirectional"))
      (node (ref "U6") (pin "P47") (pinfunction "IO_L48N_RDWR_B_VREF_2_P47") (pintype "bidirectional"))
    )
    (net (code "193") (name "{slash}MREQ_5") (class "Default")
      (node (ref "14A") (pin "1") (pinfunction "P_1") (pintype "passive"))
      (node (ref "IC3") (pin "7") (pinfunction "A6_7") (pintype "bidirectional"))
    )
    (net (code "194") (name "{slash}NMI") (class "Default")
      (node (ref "12A") (pin "1") (pinfunction "P_1") (pintype "passive"))
    )
    (net (code "195") (name "{slash}OE_OL") (class "Default")
      (node (ref "U3") (pin "77") (pinfunction "PA15_77") (pintype "bidirectional"))
      (node (ref "U6") (pin "P12") (pinfunction "IO_L49P_3_P12") (pintype "bidirectional"))
    )
    (net (code "196") (name "{slash}RD") (class "Default")
      (node (ref "IC3") (pin "15") (pinfunction "B4_15") (pintype "bidirectional"))
      (node (ref "U6") (pin "P105") (pinfunction "IO_L1P_1_P105") (pintype "bidirectional"))
    )
    (net (code "197") (name "{slash}RD_5") (class "Default")
      (node (ref "16A") (pin "1") (pinfunction "P_1") (pintype "passive"))
      (node (ref "IC3") (pin "5") (pinfunction "A4_5") (pintype "bidirectional"))
    )
    (net (code "198") (name "{slash}RESET") (class "Default")
      (node (ref "21A") (pin "1") (pinfunction "P_1") (pintype "passive"))
      (node (ref "U3") (pin "96") (pinfunction "PB9_96") (pintype "bidirectional"))
    )
    (net (code "199") (name "{slash}RESET_FPGA") (class "Default")
      (node (ref "U3") (pin "95") (pinfunction "PB8_95") (pintype "bidirectional"))
      (node (ref "U6") (pin "P140") (pinfunction "IO_L3P_0_P140") (pintype "bidirectional"))
    )
    (net (code "200") (name "{slash}RFSH") (class "Default")
      (node (ref "IC3") (pin "18") (pinfunction "B1_18") (pintype "bidirectional"))
      (node (ref "U6") (pin "P74") (pinfunction "IO_L74N_DOUT_BUSY_1_P74") (pintype "bidirectional"))
    )
    (net (code "201") (name "{slash}RFSH_5") (class "Default")
      (node (ref "23A") (pin "1") (pinfunction "P_1") (pintype "passive"))
      (node (ref "IC3") (pin "2") (pinfunction "A1_2") (pintype "bidirectional"))
    )
    (net (code "202") (name "{slash}WAIT") (class "Default")
      (node (ref "19A") (pin "1") (pinfunction "P_1") (pintype "passive"))
      (node (ref "U3") (pin "23") (pinfunction "PA0_23") (pintype "bidirectional"))
    )
    (net (code "203") (name "{slash}WR") (class "Default")
      (node (ref "IC3") (pin "16") (pinfunction "B3_16") (pintype "bidirectional"))
      (node (ref "U6") (pin "P58") (pinfunction "IO_L14P_D11_2_P58") (pintype "bidirectional"))
    )
    (net (code "204") (name "{slash}WR'") (class "Default")
      (node (ref "U2") (pin "29") (pinfunction "WE_29") (pintype "input"))
      (node (ref "U3") (pin "26") (pinfunction "PA3_26") (pintype "bidirectional"))
      (node (ref "U6") (pin "P102") (pinfunction "IO_L32P_1_P102") (pintype "bidirectional"))
    )
    (net (code "205") (name "{slash}WR_5") (class "Default")
      (node (ref "17A") (pin "1") (pinfunction "P_1") (pintype "passive"))
      (node (ref "IC3") (pin "4") (pinfunction "A3_4") (pintype "bidirectional"))
    )
    (net (code "206") (name "~{RESET}") (class "Default")
      (node (ref "C5") (pin "2") (pinfunction "2_2") (pintype "passive"))
      (node (ref "R15") (pin "1") (pinfunction "1_1") (pintype "passive"))
      (node (ref "S1") (pin "2") (pinfunction "S_2") (pintype "passive"))
      (node (ref "U3") (pin "14") (pinfunction "NRST_14") (pintype "bidirectional"))
    )
  )
)
